# XMICRO-6502.net
KiCad netlist of a schematic drawn in EAGLE
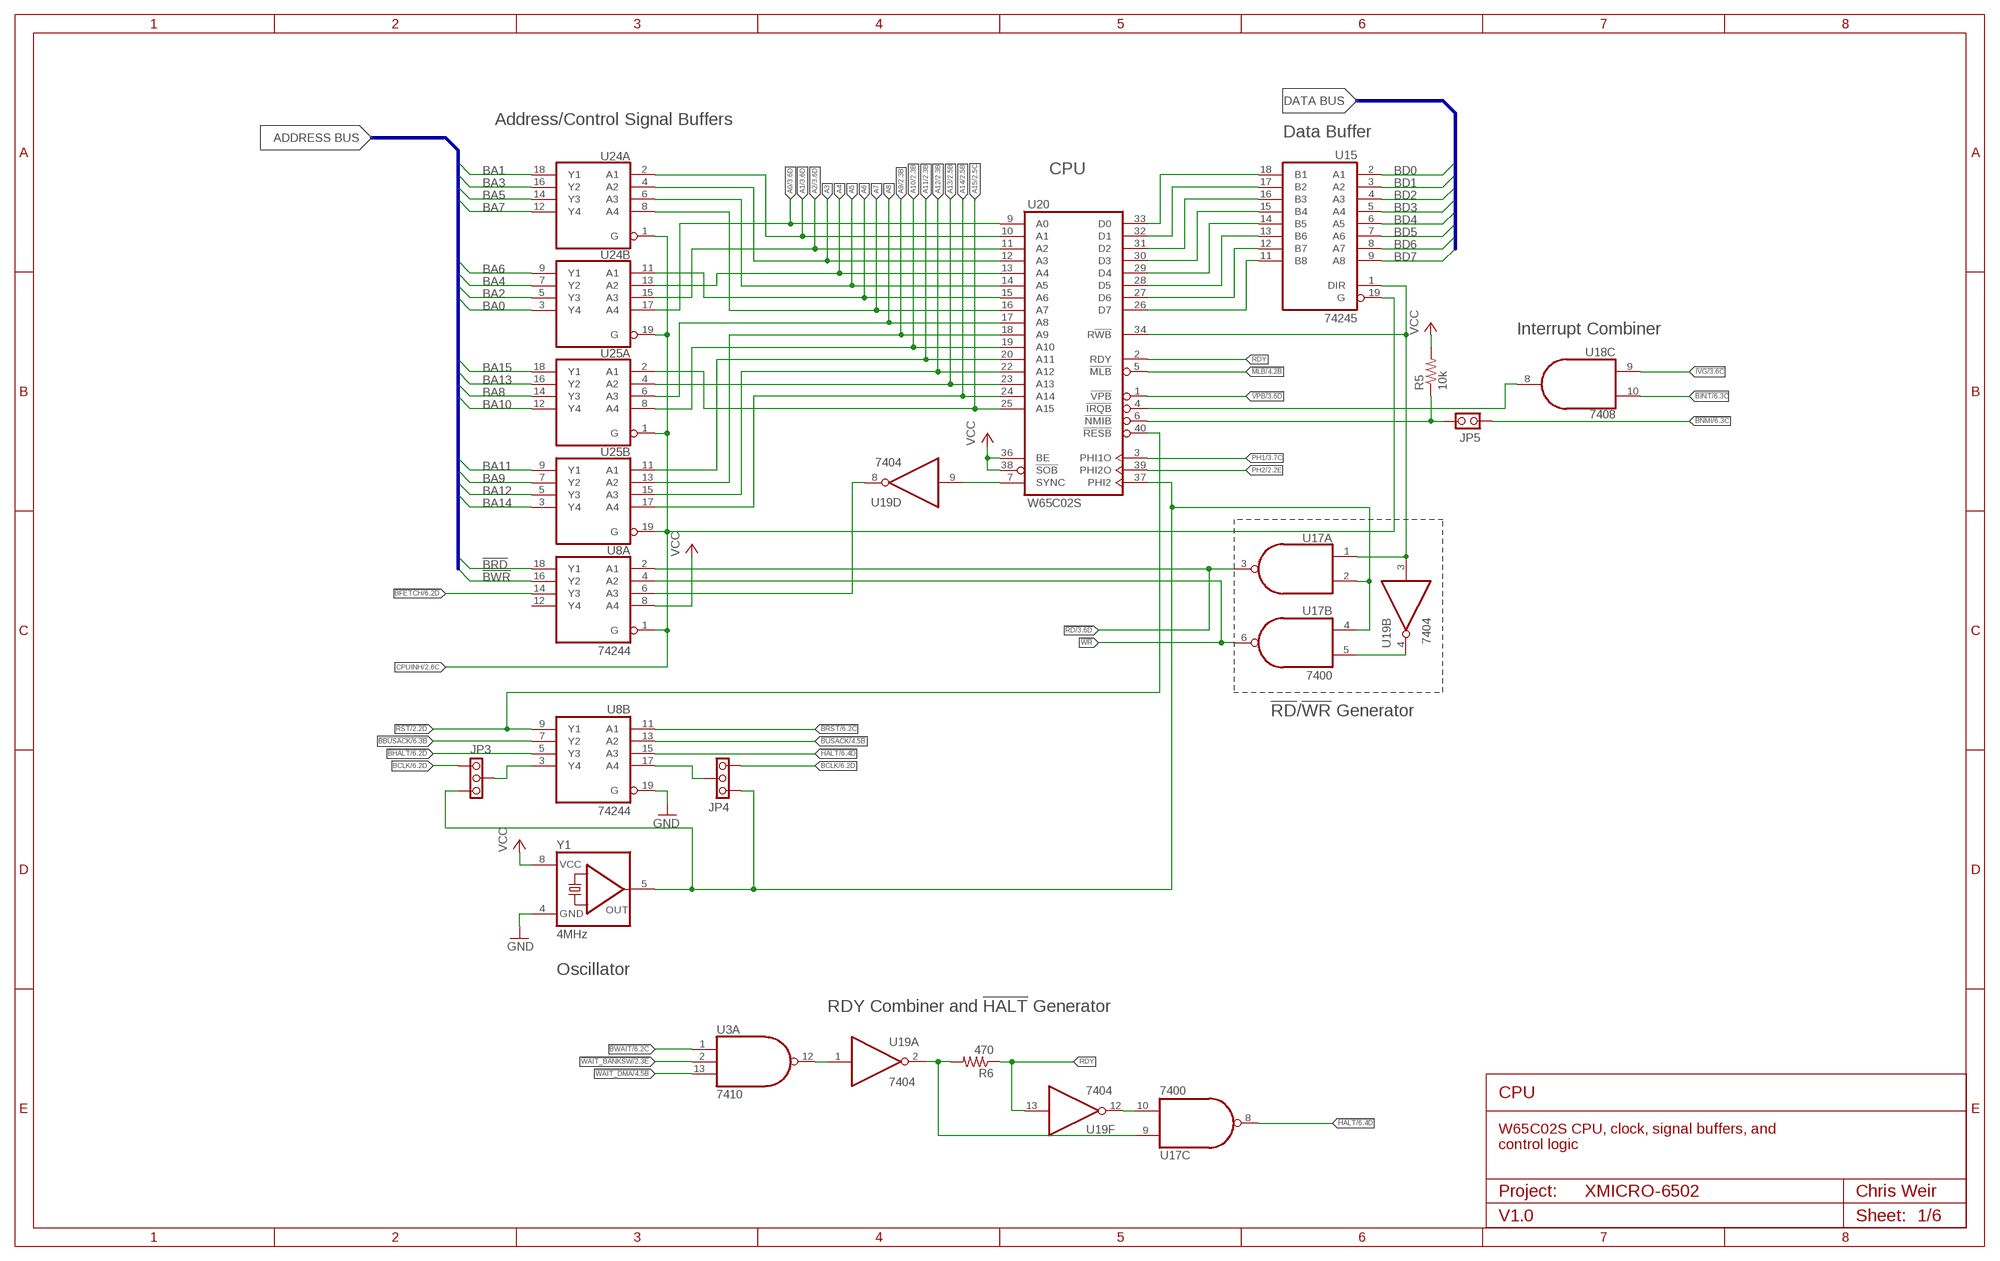
[diagram p0: schematic, sheet 1]
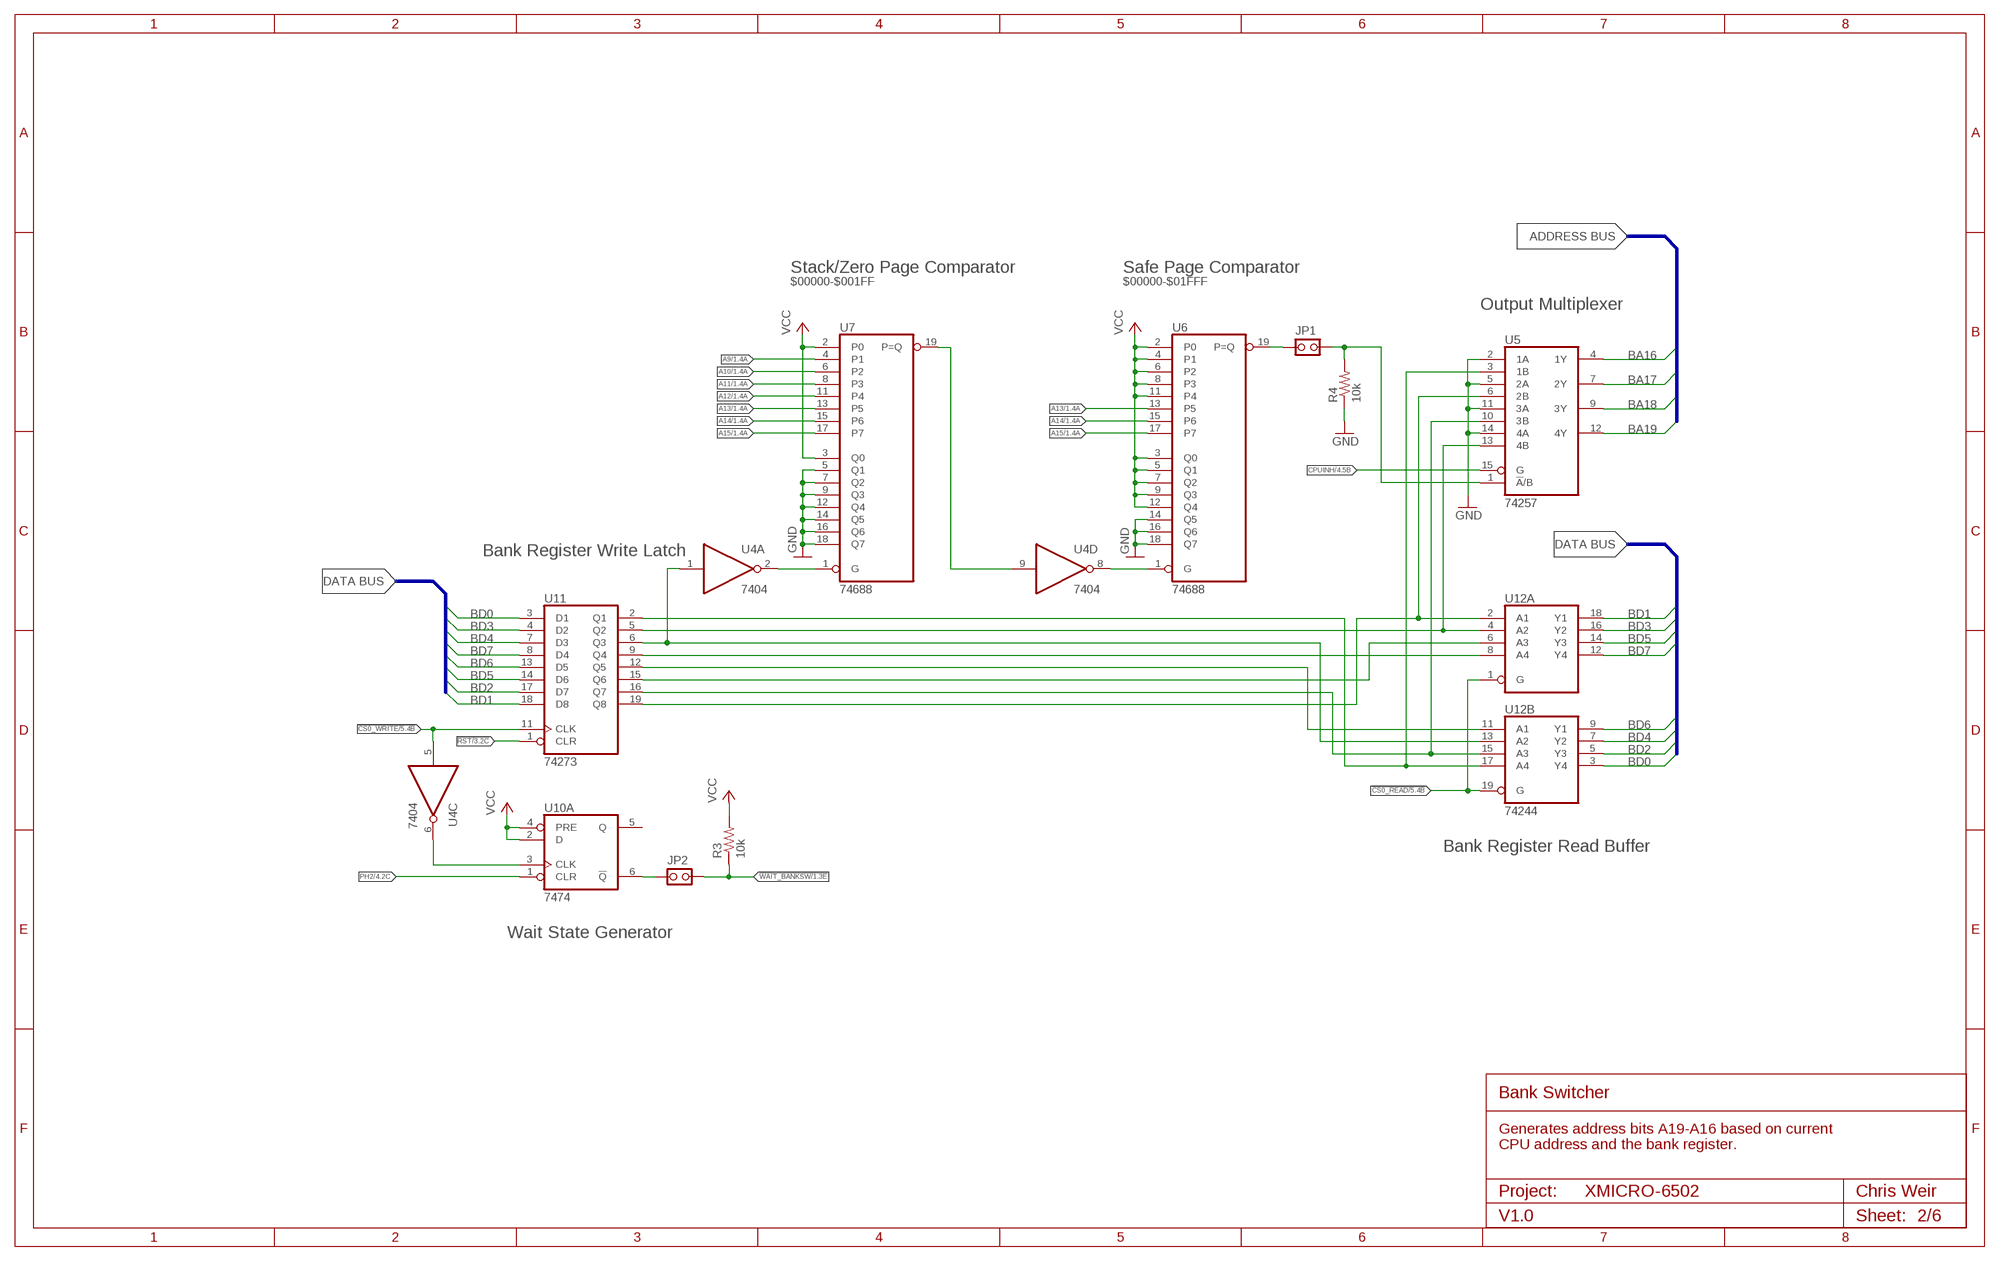
[diagram p1: schematic, sheet 2]
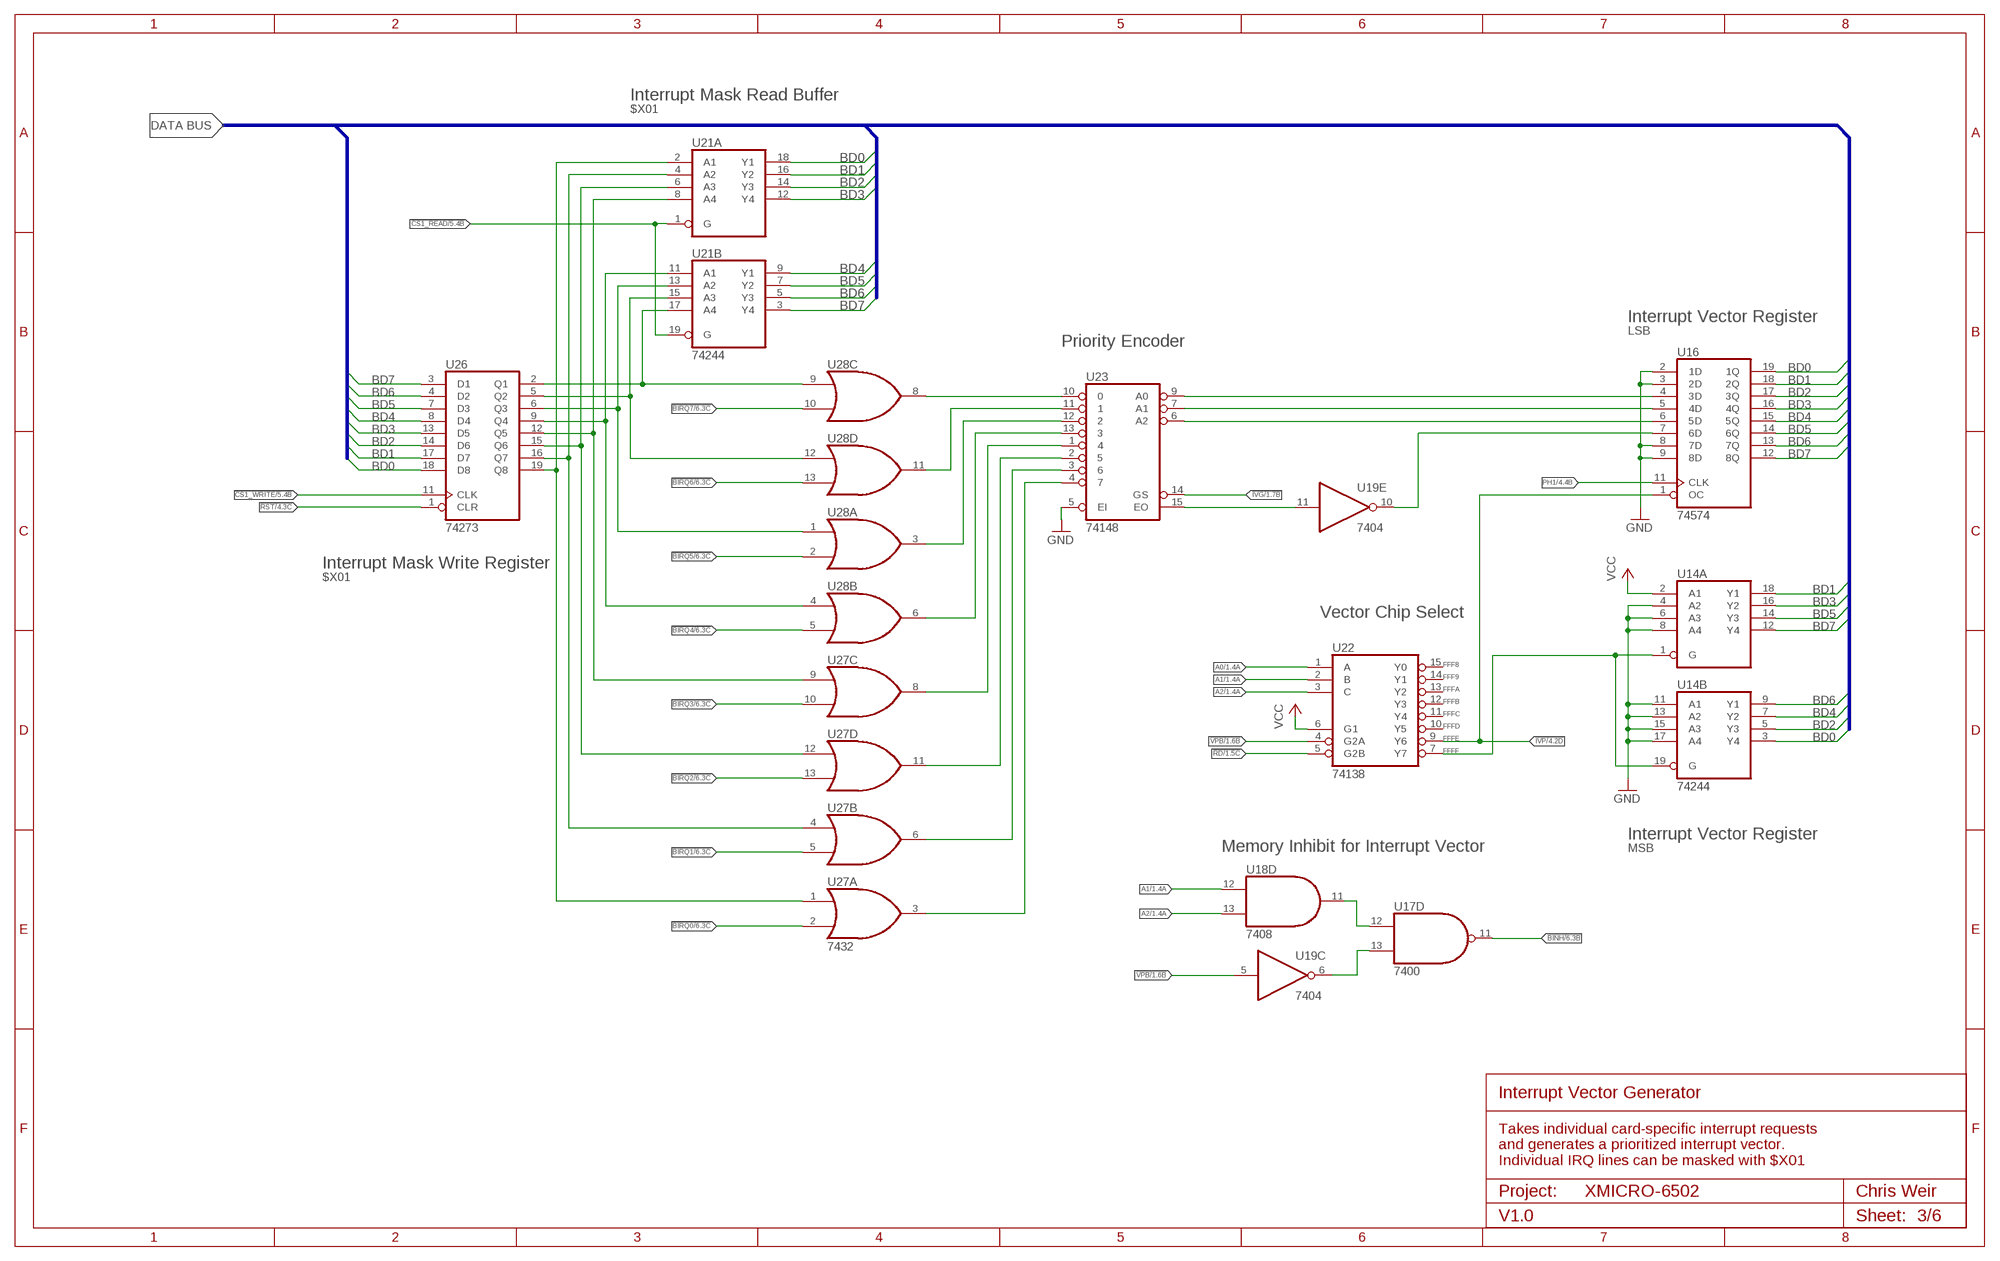
[diagram p2: schematic, sheet 3]
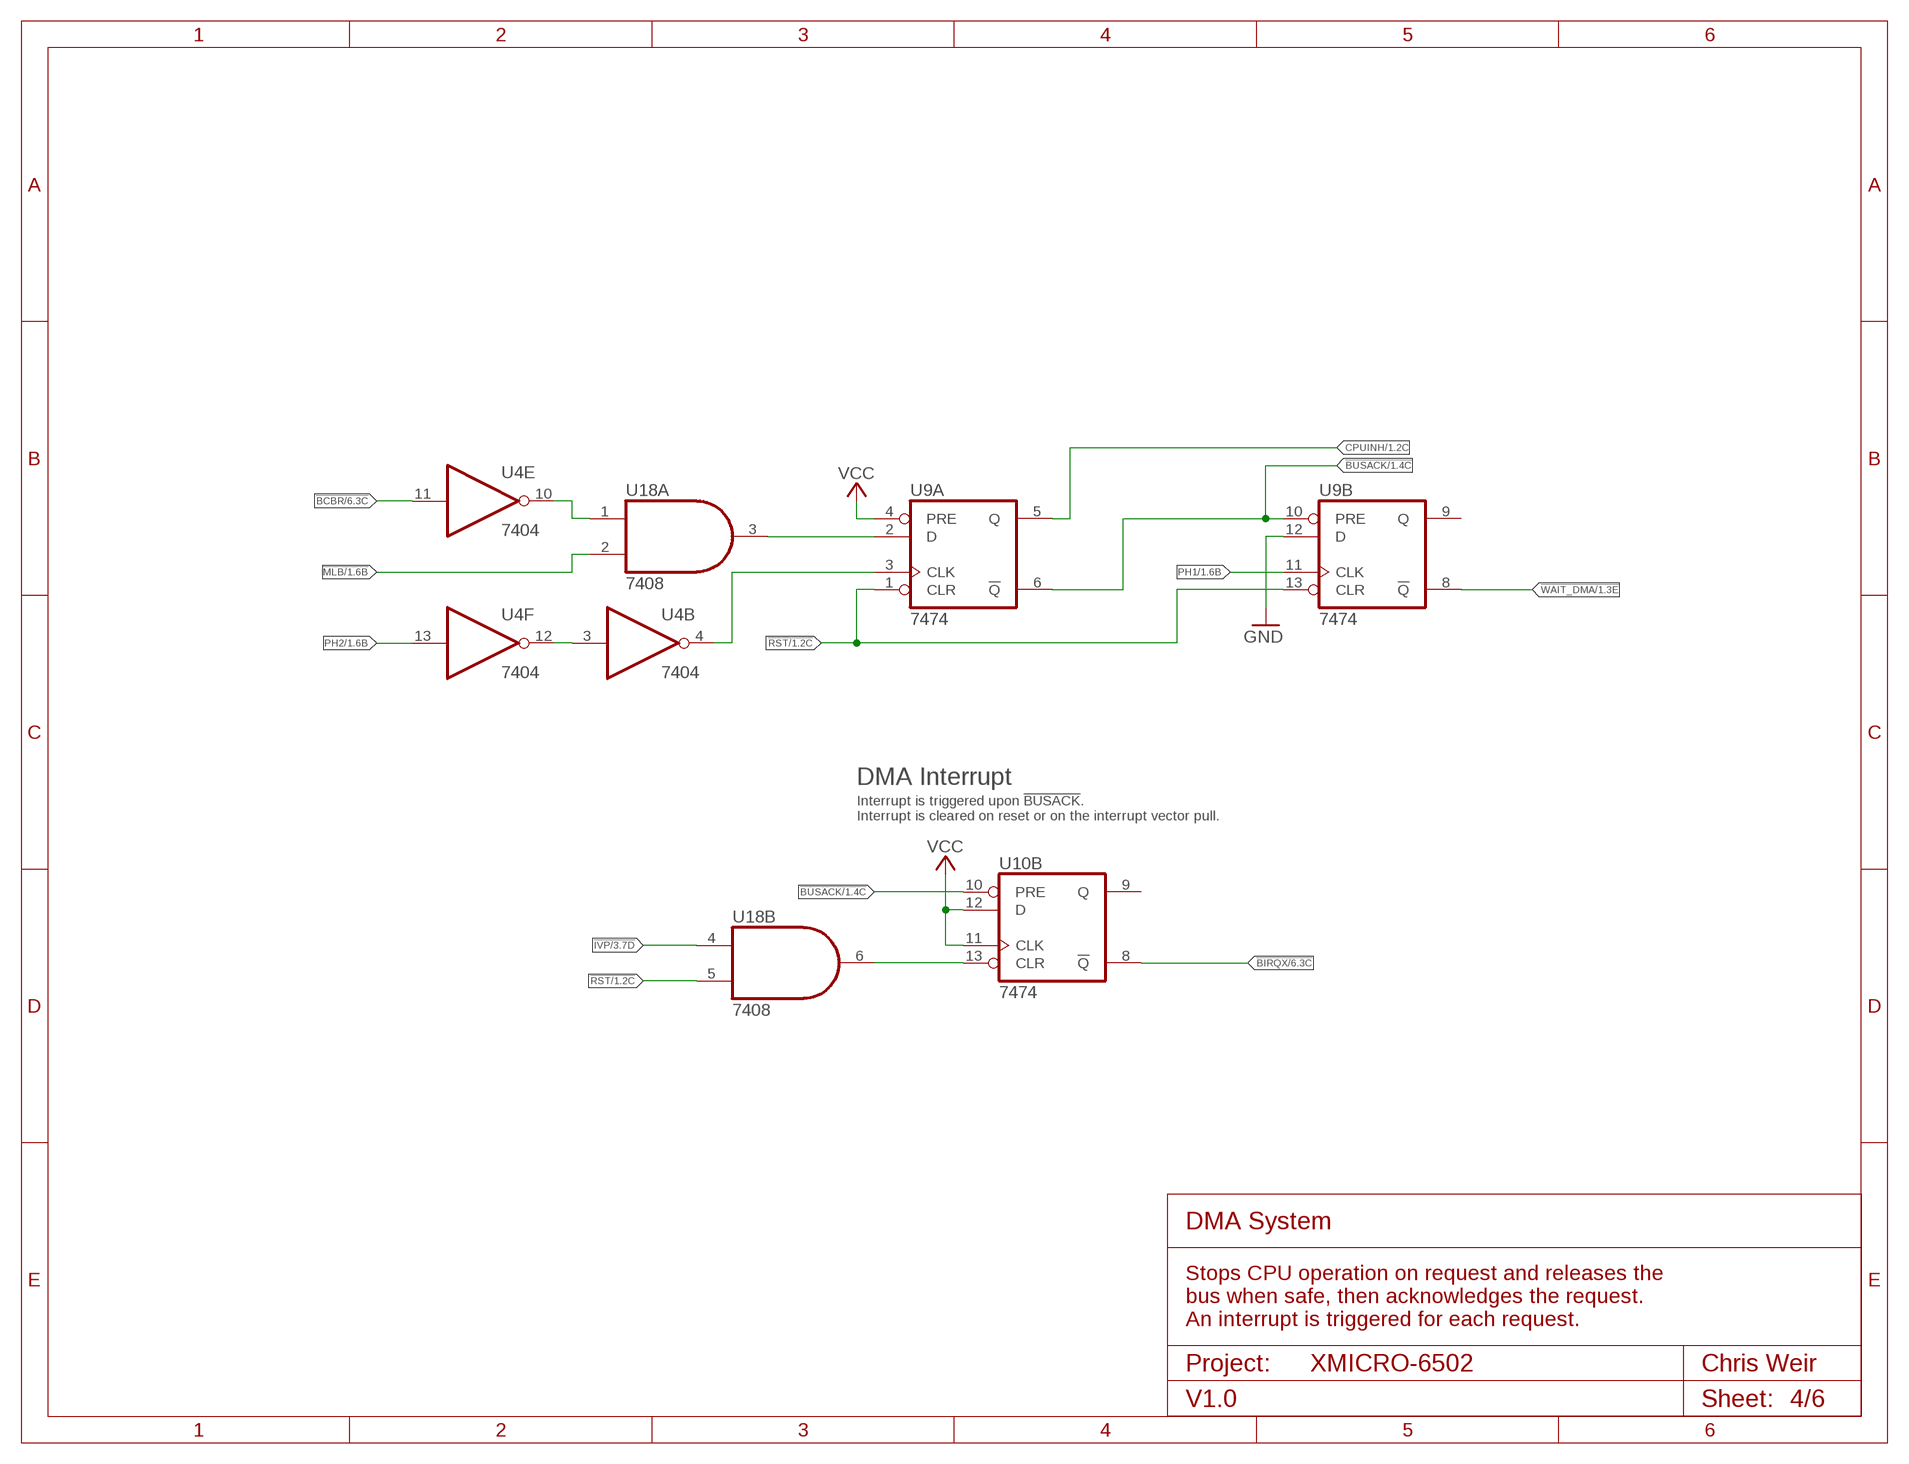
[diagram p3: schematic, sheet 4]
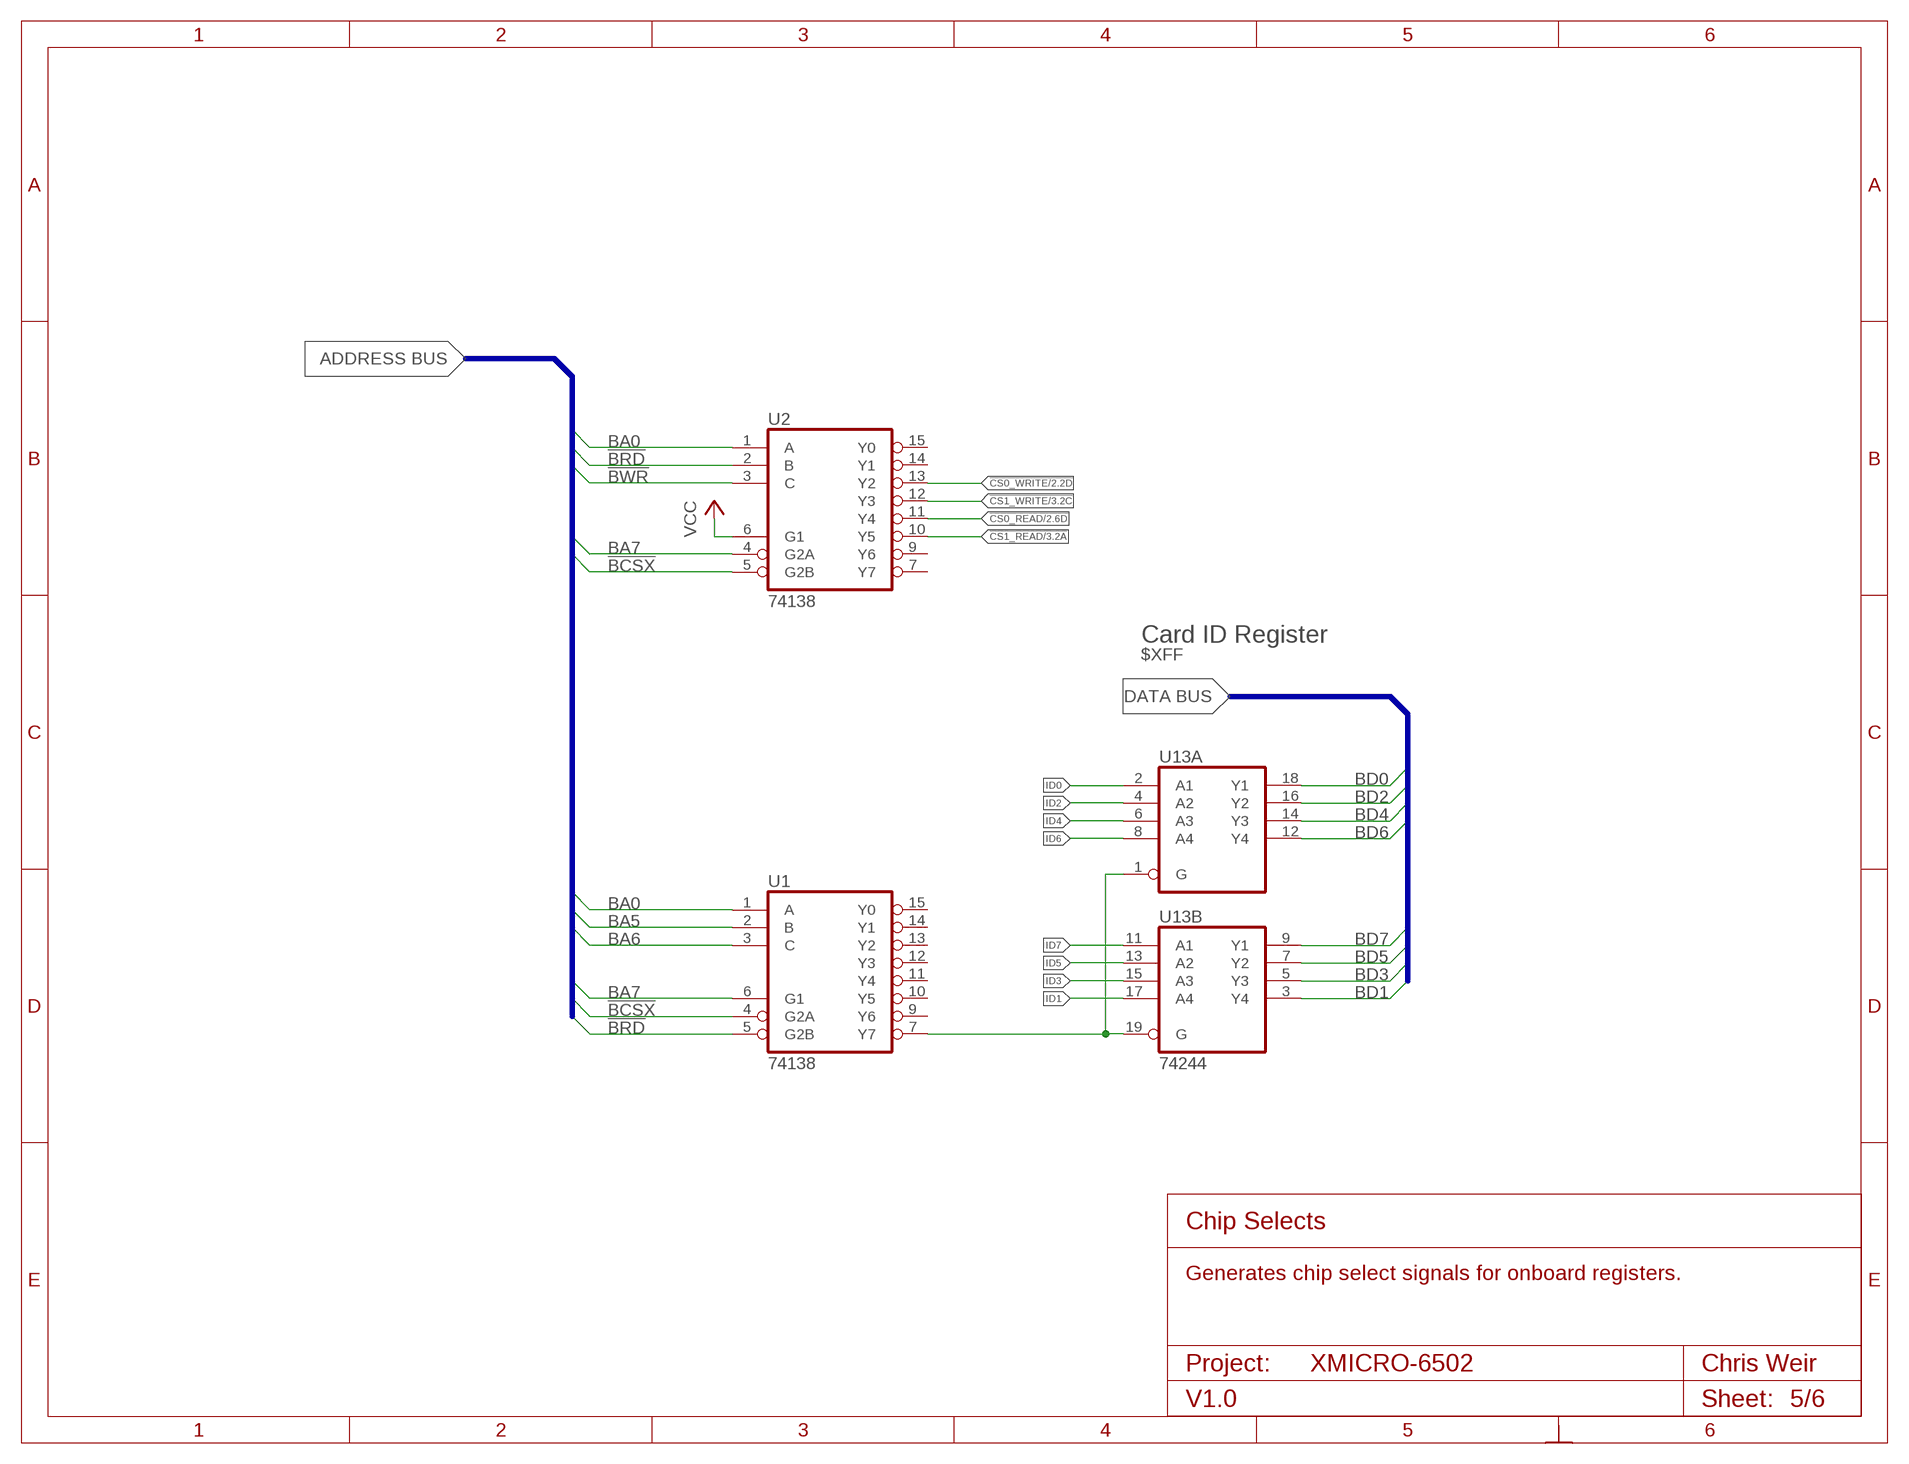
[diagram p4: schematic, sheet 5]
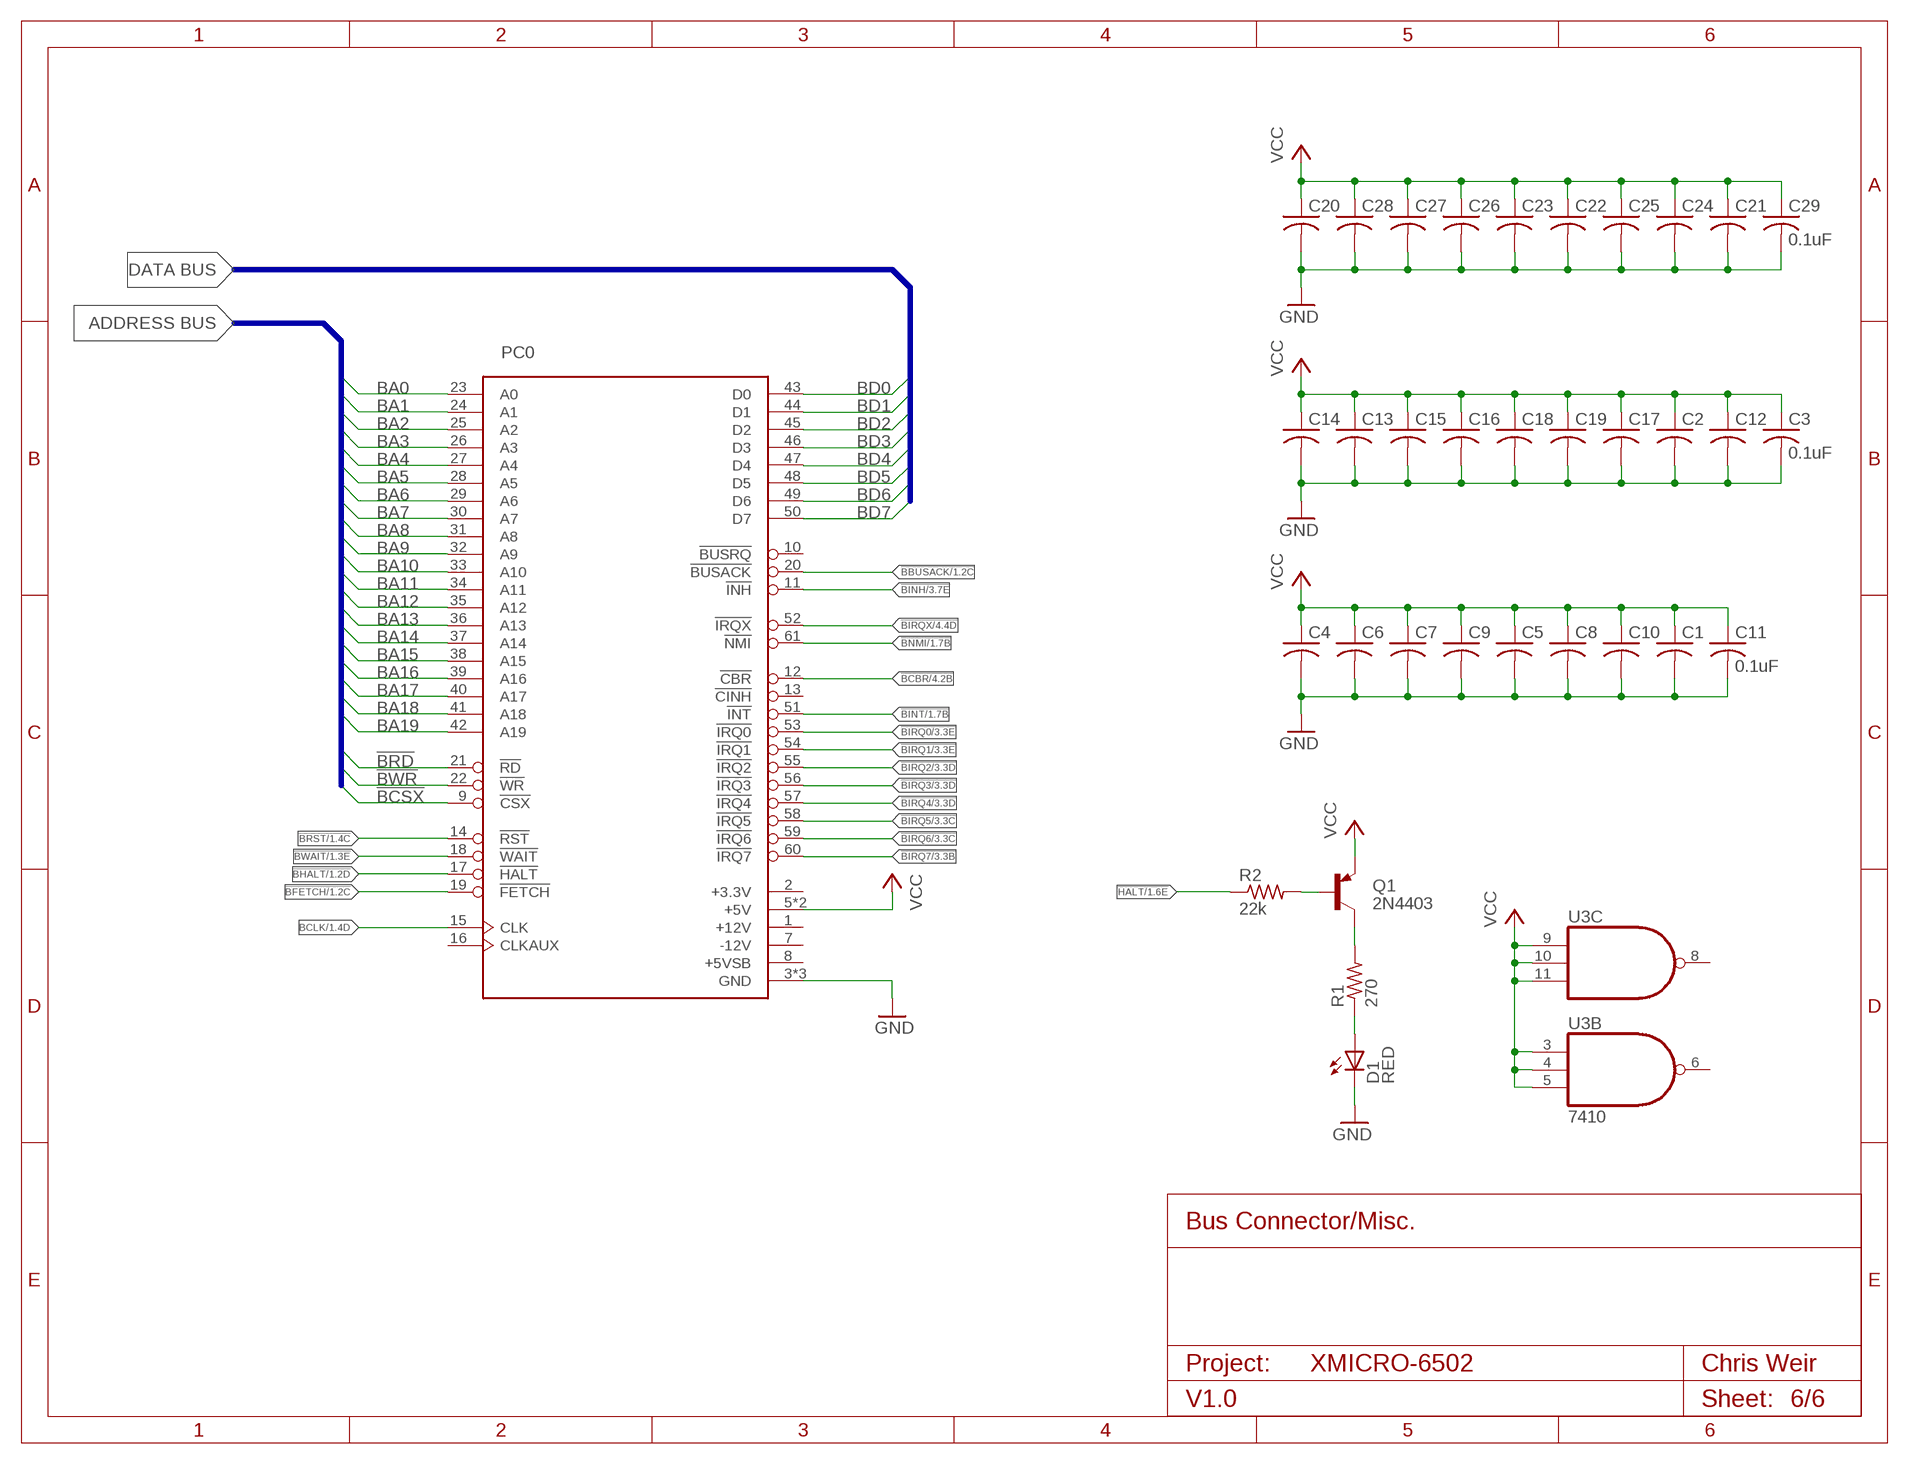
[diagram p5: schematic, sheet 6]

(export (version "E")
  (design (tool "Eeschema 10.0.6"))
  (components
    (comp (ref "JP1")
      (value "PINHD-1X2THRU")
      (footprint "eagle-import:1X02")
      (libsource (lib "eagle-import") (part "PINHD-1X2THRU"))
    )
    (comp (ref "JP2")
      (value "PINHD-1X2THRU")
      (footprint "eagle-import:1X02")
      (libsource (lib "eagle-import") (part "PINHD-1X2THRU"))
    )
    (comp (ref "R3")
      (value "10k")
      (footprint "eagle-import:0207_10")
      (libsource (lib "eagle-import") (part "R-US_0207/10"))
    )
    (comp (ref "R4")
      (value "10k")
      (footprint "eagle-import:0207_10")
      (libsource (lib "eagle-import") (part "R-US_0207/10"))
    )
    (comp (ref "U4")
      (value "7404")
      (footprint "eagle-import:DIL14")
      (libsource (lib "eagle-import") (part "7404NLS"))
    )
    (comp (ref "U5")
      (value "74257")
      (footprint "eagle-import:DIL16")
      (libsource (lib "eagle-import") (part "74257NLS"))
    )
    (comp (ref "U6")
      (value "74688")
      (footprint "eagle-import:DIL20")
      (libsource (lib "eagle-import") (part "74688NLS"))
    )
    (comp (ref "U7")
      (value "74688")
      (footprint "eagle-import:DIL20")
      (libsource (lib "eagle-import") (part "74688NLS"))
    )
    (comp (ref "U10")
      (value "7474")
      (footprint "eagle-import:DIL14")
      (libsource (lib "eagle-import") (part "7474NLS"))
    )
    (comp (ref "U11")
      (value "74273")
      (footprint "eagle-import:DIL20")
      (libsource (lib "eagle-import") (part "74273N"))
    )
    (comp (ref "U12")
      (value "74244")
      (footprint "eagle-import:DIL20")
      (libsource (lib "eagle-import") (part "74244NLS"))
    )
    (comp (ref "U14")
      (value "74244")
      (footprint "eagle-import:DIL20")
      (libsource (lib "eagle-import") (part "74244NLS"))
    )
    (comp (ref "U16")
      (value "74574")
      (footprint "eagle-import:DIL20")
      (libsource (lib "eagle-import") (part "74574NHC"))
    )
    (comp (ref "U17")
      (value "7400")
      (footprint "eagle-import:DIL14")
      (libsource (lib "eagle-import") (part "7400NLS"))
    )
    (comp (ref "U18")
      (value "7408")
      (footprint "eagle-import:DIL14")
      (libsource (lib "eagle-import") (part "7408NLS"))
    )
    (comp (ref "U19")
      (value "7404")
      (footprint "eagle-import:DIL14")
      (libsource (lib "eagle-import") (part "7404NLS"))
    )
    (comp (ref "U21")
      (value "74244")
      (footprint "eagle-import:DIL20")
      (libsource (lib "eagle-import") (part "74244NLS"))
    )
    (comp (ref "U22")
      (value "74138")
      (footprint "eagle-import:DIL16")
      (libsource (lib "eagle-import") (part "74138NLS"))
    )
    (comp (ref "U23")
      (value "74148")
      (footprint "eagle-import:DIL16")
      (libsource (lib "eagle-import") (part "74148NLS"))
    )
    (comp (ref "U26")
      (value "74273")
      (footprint "eagle-import:DIL20")
      (libsource (lib "eagle-import") (part "74273N"))
    )
    (comp (ref "U27")
      (value "7432")
      (footprint "eagle-import:DIL14")
      (libsource (lib "eagle-import") (part "7432NLS"))
    )
    (comp (ref "U28")
      (value "7432")
      (footprint "eagle-import:DIL14")
      (libsource (lib "eagle-import") (part "7432NLS"))
    )
    (comp (ref "U1")
      (value "74138")
      (footprint "eagle-import:DIL16")
      (libsource (lib "eagle-import") (part "74138NLS"))
    )
    (comp (ref "U2")
      (value "74138")
      (footprint "eagle-import:DIL16")
      (libsource (lib "eagle-import") (part "74138NLS"))
    )
    (comp (ref "U13")
      (value "74244")
      (footprint "eagle-import:DIL20")
      (libsource (lib "eagle-import") (part "74244NLS"))
    )
    (comp (ref "C1")
      (value "0.1uF")
      (footprint "eagle-import:C025-024X044")
      (libsource (lib "eagle-import") (part "C-US025-024X044"))
    )
    (comp (ref "C2")
      (value "0.1uF")
      (footprint "eagle-import:C025-024X044")
      (libsource (lib "eagle-import") (part "C-US025-024X044"))
    )
    (comp (ref "C3")
      (value "0.1uF")
      (footprint "eagle-import:C025-024X044")
      (libsource (lib "eagle-import") (part "C-US025-024X044"))
    )
    (comp (ref "C4")
      (value "0.1uF")
      (footprint "eagle-import:C025-024X044")
      (libsource (lib "eagle-import") (part "C-US025-024X044"))
    )
    (comp (ref "C5")
      (value "0.1uF")
      (footprint "eagle-import:C025-024X044")
      (libsource (lib "eagle-import") (part "C-US025-024X044"))
    )
    (comp (ref "C6")
      (value "0.1uF")
      (footprint "eagle-import:C025-024X044")
      (libsource (lib "eagle-import") (part "C-US025-024X044"))
    )
    (comp (ref "C7")
      (value "0.1uF")
      (footprint "eagle-import:C025-024X044")
      (libsource (lib "eagle-import") (part "C-US025-024X044"))
    )
    (comp (ref "C8")
      (value "0.1uF")
      (footprint "eagle-import:C025-024X044")
      (libsource (lib "eagle-import") (part "C-US025-024X044"))
    )
    (comp (ref "C9")
      (value "0.1uF")
      (footprint "eagle-import:C025-024X044")
      (libsource (lib "eagle-import") (part "C-US025-024X044"))
    )
    (comp (ref "C10")
      (value "0.1uF")
      (footprint "eagle-import:C025-024X044")
      (libsource (lib "eagle-import") (part "C-US025-024X044"))
    )
    (comp (ref "C11")
      (value "0.1uF")
      (footprint "eagle-import:C025-024X044")
      (libsource (lib "eagle-import") (part "C-US025-024X044"))
    )
    (comp (ref "C12")
      (value "0.1uF")
      (footprint "eagle-import:C025-024X044")
      (libsource (lib "eagle-import") (part "C-US025-024X044"))
    )
    (comp (ref "C13")
      (value "0.1uF")
      (footprint "eagle-import:C025-024X044")
      (libsource (lib "eagle-import") (part "C-US025-024X044"))
    )
    (comp (ref "C14")
      (value "0.1uF")
      (footprint "eagle-import:C025-024X044")
      (libsource (lib "eagle-import") (part "C-US025-024X044"))
    )
    (comp (ref "C15")
      (value "0.1uF")
      (footprint "eagle-import:C025-024X044")
      (libsource (lib "eagle-import") (part "C-US025-024X044"))
    )
    (comp (ref "C16")
      (value "0.1uF")
      (footprint "eagle-import:C025-024X044")
      (libsource (lib "eagle-import") (part "C-US025-024X044"))
    )
    (comp (ref "C17")
      (value "0.1uF")
      (footprint "eagle-import:C025-024X044")
      (libsource (lib "eagle-import") (part "C-US025-024X044"))
    )
    (comp (ref "C18")
      (value "0.1uF")
      (footprint "eagle-import:C025-024X044")
      (libsource (lib "eagle-import") (part "C-US025-024X044"))
    )
    (comp (ref "C19")
      (value "0.1uF")
      (footprint "eagle-import:C025-024X044")
      (libsource (lib "eagle-import") (part "C-US025-024X044"))
    )
    (comp (ref "C20")
      (value "0.1uF")
      (footprint "eagle-import:C025-024X044")
      (libsource (lib "eagle-import") (part "C-US025-024X044"))
    )
    (comp (ref "C21")
      (value "0.1uF")
      (footprint "eagle-import:C025-024X044")
      (libsource (lib "eagle-import") (part "C-US025-024X044"))
    )
    (comp (ref "C22")
      (value "0.1uF")
      (footprint "eagle-import:C025-024X044")
      (libsource (lib "eagle-import") (part "C-US025-024X044"))
    )
    (comp (ref "C23")
      (value "0.1uF")
      (footprint "eagle-import:C025-024X044")
      (libsource (lib "eagle-import") (part "C-US025-024X044"))
    )
    (comp (ref "C24")
      (value "0.1uF")
      (footprint "eagle-import:C025-024X044")
      (libsource (lib "eagle-import") (part "C-US025-024X044"))
    )
    (comp (ref "C25")
      (value "0.1uF")
      (footprint "eagle-import:C025-024X044")
      (libsource (lib "eagle-import") (part "C-US025-024X044"))
    )
    (comp (ref "C26")
      (value "0.1uF")
      (footprint "eagle-import:C025-024X044")
      (libsource (lib "eagle-import") (part "C-US025-024X044"))
    )
    (comp (ref "C27")
      (value "0.1uF")
      (footprint "eagle-import:C025-024X044")
      (libsource (lib "eagle-import") (part "C-US025-024X044"))
    )
    (comp (ref "C28")
      (value "0.1uF")
      (footprint "eagle-import:C025-024X044")
      (libsource (lib "eagle-import") (part "C-US025-024X044"))
    )
    (comp (ref "C29")
      (value "0.1uF")
      (footprint "eagle-import:C025-024X044")
      (libsource (lib "eagle-import") (part "C-US025-024X044"))
    )
    (comp (ref "D1")
      (value "RED")
      (footprint "eagle-import:LED5MM")
      (libsource (lib "eagle-import") (part "LED5MM"))
    )
    (comp (ref "PC0")
      (value "XMICRO-BUS-EDGE62M")
      (footprint "eagle-import:EDGE62M")
      (libsource (lib "eagle-import") (part "XMICRO-BUS-EDGE62M"))
    )
    (comp (ref "Q1")
      (value "2N4403")
      (footprint "eagle-import:TO92")
      (libsource (lib "eagle-import") (part "TRANSISTOR-PNP-2N4403"))
    )
    (comp (ref "R1")
      (value "270")
      (footprint "eagle-import:0207_10")
      (libsource (lib "eagle-import") (part "R-US_0207/10"))
    )
    (comp (ref "R2")
      (value "22k")
      (footprint "eagle-import:0207_10")
      (libsource (lib "eagle-import") (part "R-US_0207/10"))
    )
    (comp (ref "U3")
      (value "7410")
      (footprint "eagle-import:DIL14")
      (libsource (lib "eagle-import") (part "7410NLS"))
    )
    (comp (ref "U9")
      (value "7474")
      (footprint "eagle-import:DIL14")
      (libsource (lib "eagle-import") (part "7474NLS"))
    )
    (comp (ref "JP3")
      (value "PINHD1X3THRU")
      (footprint "eagle-import:1X03")
      (libsource (lib "eagle-import") (part "PINHD1X3THRU"))
    )
    (comp (ref "JP4")
      (value "PINHD1X3THRU")
      (footprint "eagle-import:1X03")
      (libsource (lib "eagle-import") (part "PINHD1X3THRU"))
    )
    (comp (ref "JP5")
      (value "PINHD-1X2THRU")
      (footprint "eagle-import:1X02")
      (libsource (lib "eagle-import") (part "PINHD-1X2THRU"))
    )
    (comp (ref "R5")
      (value "10k")
      (footprint "eagle-import:0207_10")
      (libsource (lib "eagle-import") (part "R-US_0207/10"))
    )
    (comp (ref "R6")
      (value "470")
      (footprint "eagle-import:0207_10")
      (libsource (lib "eagle-import") (part "R-US_0207/10"))
    )
    (comp (ref "U8")
      (value "74244")
      (footprint "eagle-import:DIL20")
      (libsource (lib "eagle-import") (part "74244NLS"))
    )
    (comp (ref "U15")
      (value "74245")
      (footprint "eagle-import:DIL20")
      (libsource (lib "eagle-import") (part "74245NLS"))
    )
    (comp (ref "U20")
      (value "W65C02S")
      (footprint "eagle-import:DIL40")
      (libsource (lib "eagle-import") (part "W65C02P"))
    )
    (comp (ref "U24")
      (value "74244")
      (footprint "eagle-import:DIL20")
      (libsource (lib "eagle-import") (part "74244NLS"))
    )
    (comp (ref "U25")
      (value "74244")
      (footprint "eagle-import:DIL20")
      (libsource (lib "eagle-import") (part "74244NLS"))
    )
    (comp (ref "Y1")
      (value "4MHz")
      (footprint "eagle-import:DIL08S")
      (libsource (lib "eagle-import") (part "QG5460"))
    )
  )
  (nets
    (net (code "2") (name "A0") (class "Default")
      (node (ref "U20") (pin "9") (pinfunction "A0_9") (pintype "output"))
      (node (ref "U22") (pin "1") (pinfunction "A_1") (pintype "input"))
      (node (ref "U24") (pin "17") (pinfunction "A4_17") (pintype "input"))
    )
    (net (code "3") (name "A1") (class "Default")
      (node (ref "U18") (pin "12") (pinfunction "I0_12") (pintype "input"))
      (node (ref "U20") (pin "10") (pinfunction "A1_10") (pintype "output"))
      (node (ref "U22") (pin "2") (pinfunction "B_2") (pintype "input"))
      (node (ref "U24") (pin "2") (pinfunction "A1_2") (pintype "input"))
    )
    (net (code "4") (name "A2") (class "Default")
      (node (ref "U18") (pin "13") (pinfunction "I1_13") (pintype "input"))
      (node (ref "U20") (pin "11") (pinfunction "A2_11") (pintype "output"))
      (node (ref "U22") (pin "3") (pinfunction "C_3") (pintype "input"))
      (node (ref "U24") (pin "15") (pinfunction "A3_15") (pintype "input"))
    )
    (net (code "5") (name "A3") (class "Default")
      (node (ref "U20") (pin "12") (pinfunction "A3_12") (pintype "output"))
      (node (ref "U24") (pin "4") (pinfunction "A2_4") (pintype "input"))
    )
    (net (code "6") (name "A4") (class "Default")
      (node (ref "U20") (pin "13") (pinfunction "A4_13") (pintype "output"))
      (node (ref "U24") (pin "13") (pinfunction "A2_13") (pintype "input"))
    )
    (net (code "7") (name "A5") (class "Default")
      (node (ref "U20") (pin "14") (pinfunction "A5_14") (pintype "output"))
      (node (ref "U24") (pin "6") (pinfunction "A3_6") (pintype "input"))
    )
    (net (code "8") (name "A6") (class "Default")
      (node (ref "U20") (pin "15") (pinfunction "A6_15") (pintype "output"))
      (node (ref "U24") (pin "11") (pinfunction "A1_11") (pintype "input"))
    )
    (net (code "9") (name "A7") (class "Default")
      (node (ref "U20") (pin "16") (pinfunction "A7_16") (pintype "output"))
      (node (ref "U24") (pin "8") (pinfunction "A4_8") (pintype "input"))
    )
    (net (code "10") (name "A8") (class "Default")
      (node (ref "U20") (pin "17") (pinfunction "A8_17") (pintype "output"))
      (node (ref "U25") (pin "6") (pinfunction "A3_6") (pintype "input"))
    )
    (net (code "11") (name "A9") (class "Default")
      (node (ref "U20") (pin "18") (pinfunction "A9_18") (pintype "output"))
      (node (ref "U25") (pin "13") (pinfunction "A2_13") (pintype "input"))
      (node (ref "U7") (pin "4") (pinfunction "P1_4") (pintype "input"))
    )
    (net (code "12") (name "A10") (class "Default")
      (node (ref "U20") (pin "19") (pinfunction "A10_19") (pintype "output"))
      (node (ref "U25") (pin "8") (pinfunction "A4_8") (pintype "input"))
      (node (ref "U7") (pin "6") (pinfunction "P2_6") (pintype "input"))
    )
    (net (code "13") (name "A11") (class "Default")
      (node (ref "U20") (pin "20") (pinfunction "A11_20") (pintype "output"))
      (node (ref "U25") (pin "11") (pinfunction "A1_11") (pintype "input"))
      (node (ref "U7") (pin "8") (pinfunction "P3_8") (pintype "input"))
    )
    (net (code "14") (name "A12") (class "Default")
      (node (ref "U20") (pin "22") (pinfunction "A12_22") (pintype "output"))
      (node (ref "U25") (pin "15") (pinfunction "A3_15") (pintype "input"))
      (node (ref "U7") (pin "11") (pinfunction "P4_11") (pintype "input"))
    )
    (net (code "15") (name "A13") (class "Default")
      (node (ref "U20") (pin "23") (pinfunction "A13_23") (pintype "output"))
      (node (ref "U25") (pin "4") (pinfunction "A2_4") (pintype "input"))
      (node (ref "U6") (pin "13") (pinfunction "P5_13") (pintype "input"))
      (node (ref "U7") (pin "13") (pinfunction "P5_13") (pintype "input"))
    )
    (net (code "16") (name "A14") (class "Default")
      (node (ref "U20") (pin "24") (pinfunction "A14_24") (pintype "output"))
      (node (ref "U25") (pin "17") (pinfunction "A4_17") (pintype "input"))
      (node (ref "U6") (pin "15") (pinfunction "P6_15") (pintype "input"))
      (node (ref "U7") (pin "15") (pinfunction "P6_15") (pintype "input"))
    )
    (net (code "17") (name "A15") (class "Default")
      (node (ref "U20") (pin "25") (pinfunction "A15_25") (pintype "output"))
      (node (ref "U25") (pin "2") (pinfunction "A1_2") (pintype "input"))
      (node (ref "U6") (pin "17") (pinfunction "P7_17") (pintype "input"))
      (node (ref "U7") (pin "17") (pinfunction "P7_17") (pintype "input"))
    )
    (net (code "18") (name "BA0") (class "Default")
      (node (ref "PC0") (pin "23") (pinfunction "A0_23") (pintype "bidirectional"))
      (node (ref "U1") (pin "1") (pinfunction "A_1") (pintype "input"))
      (node (ref "U2") (pin "1") (pinfunction "A_1") (pintype "input"))
      (node (ref "U24") (pin "3") (pinfunction "Y4_3") (pintype "tri_state"))
    )
    (net (code "19") (name "BA1") (class "Default")
      (node (ref "PC0") (pin "24") (pinfunction "A1_24") (pintype "bidirectional"))
      (node (ref "U24") (pin "18") (pinfunction "Y1_18") (pintype "tri_state"))
    )
    (net (code "20") (name "BA2") (class "Default")
      (node (ref "PC0") (pin "25") (pinfunction "A2_25") (pintype "bidirectional"))
      (node (ref "U24") (pin "5") (pinfunction "Y3_5") (pintype "tri_state"))
    )
    (net (code "21") (name "BA3") (class "Default")
      (node (ref "PC0") (pin "26") (pinfunction "A3_26") (pintype "bidirectional"))
      (node (ref "U24") (pin "16") (pinfunction "Y2_16") (pintype "tri_state"))
    )
    (net (code "22") (name "BA4") (class "Default")
      (node (ref "PC0") (pin "27") (pinfunction "A4_27") (pintype "bidirectional"))
      (node (ref "U24") (pin "7") (pinfunction "Y2_7") (pintype "tri_state"))
    )
    (net (code "23") (name "BA5") (class "Default")
      (node (ref "PC0") (pin "28") (pinfunction "A5_28") (pintype "bidirectional"))
      (node (ref "U1") (pin "2") (pinfunction "B_2") (pintype "input"))
      (node (ref "U24") (pin "14") (pinfunction "Y3_14") (pintype "tri_state"))
    )
    (net (code "24") (name "BA6") (class "Default")
      (node (ref "PC0") (pin "29") (pinfunction "A6_29") (pintype "bidirectional"))
      (node (ref "U1") (pin "3") (pinfunction "C_3") (pintype "input"))
      (node (ref "U24") (pin "9") (pinfunction "Y1_9") (pintype "tri_state"))
    )
    (net (code "25") (name "BA7") (class "Default")
      (node (ref "PC0") (pin "30") (pinfunction "A7_30") (pintype "bidirectional"))
      (node (ref "U1") (pin "6") (pinfunction "G1_6") (pintype "input"))
      (node (ref "U2") (pin "4") (pinfunction "G2A_4") (pintype "input"))
      (node (ref "U24") (pin "12") (pinfunction "Y4_12") (pintype "tri_state"))
    )
    (net (code "26") (name "BA8") (class "Default")
      (node (ref "PC0") (pin "31") (pinfunction "A8_31") (pintype "bidirectional"))
      (node (ref "U25") (pin "14") (pinfunction "Y3_14") (pintype "tri_state"))
    )
    (net (code "27") (name "BA9") (class "Default")
      (node (ref "PC0") (pin "32") (pinfunction "A9_32") (pintype "bidirectional"))
      (node (ref "U25") (pin "7") (pinfunction "Y2_7") (pintype "tri_state"))
    )
    (net (code "28") (name "BA10") (class "Default")
      (node (ref "PC0") (pin "33") (pinfunction "A10_33") (pintype "bidirectional"))
      (node (ref "U25") (pin "12") (pinfunction "Y4_12") (pintype "tri_state"))
    )
    (net (code "29") (name "BA11") (class "Default")
      (node (ref "PC0") (pin "34") (pinfunction "A11_34") (pintype "bidirectional"))
      (node (ref "U25") (pin "9") (pinfunction "Y1_9") (pintype "tri_state"))
    )
    (net (code "30") (name "BA12") (class "Default")
      (node (ref "PC0") (pin "35") (pinfunction "A12_35") (pintype "bidirectional"))
      (node (ref "U25") (pin "5") (pinfunction "Y3_5") (pintype "tri_state"))
    )
    (net (code "31") (name "BA13") (class "Default")
      (node (ref "PC0") (pin "36") (pinfunction "A13_36") (pintype "bidirectional"))
      (node (ref "U25") (pin "16") (pinfunction "Y2_16") (pintype "tri_state"))
    )
    (net (code "32") (name "BA14") (class "Default")
      (node (ref "PC0") (pin "37") (pinfunction "A14_37") (pintype "bidirectional"))
      (node (ref "U25") (pin "3") (pinfunction "Y4_3") (pintype "tri_state"))
    )
    (net (code "33") (name "BA15") (class "Default")
      (node (ref "PC0") (pin "38") (pinfunction "A15_38") (pintype "bidirectional"))
      (node (ref "U25") (pin "18") (pinfunction "Y1_18") (pintype "tri_state"))
    )
    (net (code "34") (name "BA16") (class "Default")
      (node (ref "PC0") (pin "39") (pinfunction "A16_39") (pintype "bidirectional"))
      (node (ref "U5") (pin "4") (pinfunction "1Y_4") (pintype "tri_state"))
    )
    (net (code "35") (name "BA17") (class "Default")
      (node (ref "PC0") (pin "40") (pinfunction "A17_40") (pintype "bidirectional"))
      (node (ref "U5") (pin "7") (pinfunction "2Y_7") (pintype "tri_state"))
    )
    (net (code "36") (name "BA18") (class "Default")
      (node (ref "PC0") (pin "41") (pinfunction "A18_41") (pintype "bidirectional"))
      (node (ref "U5") (pin "9") (pinfunction "3Y_9") (pintype "tri_state"))
    )
    (net (code "37") (name "BA19") (class "Default")
      (node (ref "PC0") (pin "42") (pinfunction "A19_42") (pintype "bidirectional"))
      (node (ref "U5") (pin "12") (pinfunction "4Y_12") (pintype "tri_state"))
    )
    (net (code "38") (name "BCLK") (class "Default")
      (node (ref "JP3") (pin "1") (pinfunction "1_1") (pintype "passive"))
      (node (ref "JP4") (pin "3") (pinfunction "3_3") (pintype "passive"))
      (node (ref "PC0") (pin "15") (pinfunction "CLK_15") (pintype "bidirectional"))
    )
    (net (code "39") (name "BD0") (class "Default")
      (node (ref "PC0") (pin "43") (pinfunction "D0_43") (pintype "bidirectional"))
      (node (ref "U11") (pin "3") (pinfunction "D1_3") (pintype "input"))
      (node (ref "U12") (pin "3") (pinfunction "Y4_3") (pintype "tri_state"))
      (node (ref "U13") (pin "18") (pinfunction "Y1_18") (pintype "tri_state"))
      (node (ref "U14") (pin "3") (pinfunction "Y4_3") (pintype "tri_state"))
      (node (ref "U15") (pin "2") (pinfunction "A1_2") (pintype "bidirectional"))
      (node (ref "U16") (pin "19") (pinfunction "1Q_19") (pintype "tri_state"))
      (node (ref "U21") (pin "18") (pinfunction "Y1_18") (pintype "tri_state"))
      (node (ref "U26") (pin "18") (pinfunction "D8_18") (pintype "input"))
    )
    (net (code "40") (name "BD1") (class "Default")
      (node (ref "PC0") (pin "44") (pinfunction "D1_44") (pintype "bidirectional"))
      (node (ref "U11") (pin "18") (pinfunction "D8_18") (pintype "input"))
      (node (ref "U12") (pin "18") (pinfunction "Y1_18") (pintype "tri_state"))
      (node (ref "U13") (pin "3") (pinfunction "Y4_3") (pintype "tri_state"))
      (node (ref "U14") (pin "18") (pinfunction "Y1_18") (pintype "tri_state"))
      (node (ref "U15") (pin "3") (pinfunction "A2_3") (pintype "bidirectional"))
      (node (ref "U16") (pin "18") (pinfunction "2Q_18") (pintype "tri_state"))
      (node (ref "U21") (pin "16") (pinfunction "Y2_16") (pintype "tri_state"))
      (node (ref "U26") (pin "17") (pinfunction "D7_17") (pintype "input"))
    )
    (net (code "41") (name "BD2") (class "Default")
      (node (ref "PC0") (pin "45") (pinfunction "D2_45") (pintype "bidirectional"))
      (node (ref "U11") (pin "17") (pinfunction "D7_17") (pintype "input"))
      (node (ref "U12") (pin "5") (pinfunction "Y3_5") (pintype "tri_state"))
      (node (ref "U13") (pin "16") (pinfunction "Y2_16") (pintype "tri_state"))
      (node (ref "U14") (pin "5") (pinfunction "Y3_5") (pintype "tri_state"))
      (node (ref "U15") (pin "4") (pinfunction "A3_4") (pintype "bidirectional"))
      (node (ref "U16") (pin "17") (pinfunction "3Q_17") (pintype "tri_state"))
      (node (ref "U21") (pin "14") (pinfunction "Y3_14") (pintype "tri_state"))
      (node (ref "U26") (pin "14") (pinfunction "D6_14") (pintype "input"))
    )
    (net (code "42") (name "BD3") (class "Default")
      (node (ref "PC0") (pin "46") (pinfunction "D3_46") (pintype "bidirectional"))
      (node (ref "U11") (pin "4") (pinfunction "D2_4") (pintype "input"))
      (node (ref "U12") (pin "16") (pinfunction "Y2_16") (pintype "tri_state"))
      (node (ref "U13") (pin "5") (pinfunction "Y3_5") (pintype "tri_state"))
      (node (ref "U14") (pin "16") (pinfunction "Y2_16") (pintype "tri_state"))
      (node (ref "U15") (pin "5") (pinfunction "A4_5") (pintype "bidirectional"))
      (node (ref "U16") (pin "16") (pinfunction "4Q_16") (pintype "tri_state"))
      (node (ref "U21") (pin "12") (pinfunction "Y4_12") (pintype "tri_state"))
      (node (ref "U26") (pin "13") (pinfunction "D5_13") (pintype "input"))
    )
    (net (code "43") (name "BD4") (class "Default")
      (node (ref "PC0") (pin "47") (pinfunction "D4_47") (pintype "bidirectional"))
      (node (ref "U11") (pin "7") (pinfunction "D3_7") (pintype "input"))
      (node (ref "U12") (pin "7") (pinfunction "Y2_7") (pintype "tri_state"))
      (node (ref "U13") (pin "14") (pinfunction "Y3_14") (pintype "tri_state"))
      (node (ref "U14") (pin "7") (pinfunction "Y2_7") (pintype "tri_state"))
      (node (ref "U15") (pin "6") (pinfunction "A5_6") (pintype "bidirectional"))
      (node (ref "U16") (pin "15") (pinfunction "5Q_15") (pintype "tri_state"))
      (node (ref "U21") (pin "9") (pinfunction "Y1_9") (pintype "tri_state"))
      (node (ref "U26") (pin "8") (pinfunction "D4_8") (pintype "input"))
    )
    (net (code "44") (name "BD5") (class "Default")
      (node (ref "PC0") (pin "48") (pinfunction "D5_48") (pintype "bidirectional"))
      (node (ref "U11") (pin "14") (pinfunction "D6_14") (pintype "input"))
      (node (ref "U12") (pin "14") (pinfunction "Y3_14") (pintype "tri_state"))
      (node (ref "U13") (pin "7") (pinfunction "Y2_7") (pintype "tri_state"))
      (node (ref "U14") (pin "14") (pinfunction "Y3_14") (pintype "tri_state"))
      (node (ref "U15") (pin "7") (pinfunction "A6_7") (pintype "bidirectional"))
      (node (ref "U16") (pin "14") (pinfunction "6Q_14") (pintype "tri_state"))
      (node (ref "U21") (pin "7") (pinfunction "Y2_7") (pintype "tri_state"))
      (node (ref "U26") (pin "7") (pinfunction "D3_7") (pintype "input"))
    )
    (net (code "45") (name "BD6") (class "Default")
      (node (ref "PC0") (pin "49") (pinfunction "D6_49") (pintype "bidirectional"))
      (node (ref "U11") (pin "13") (pinfunction "D5_13") (pintype "input"))
      (node (ref "U12") (pin "9") (pinfunction "Y1_9") (pintype "tri_state"))
      (node (ref "U13") (pin "12") (pinfunction "Y4_12") (pintype "tri_state"))
      (node (ref "U14") (pin "9") (pinfunction "Y1_9") (pintype "tri_state"))
      (node (ref "U15") (pin "8") (pinfunction "A7_8") (pintype "bidirectional"))
      (node (ref "U16") (pin "13") (pinfunction "7Q_13") (pintype "tri_state"))
      (node (ref "U21") (pin "5") (pinfunction "Y3_5") (pintype "tri_state"))
      (node (ref "U26") (pin "4") (pinfunction "D2_4") (pintype "input"))
    )
    (net (code "46") (name "BD7") (class "Default")
      (node (ref "PC0") (pin "50") (pinfunction "D7_50") (pintype "bidirectional"))
      (node (ref "U11") (pin "8") (pinfunction "D4_8") (pintype "input"))
      (node (ref "U12") (pin "12") (pinfunction "Y4_12") (pintype "tri_state"))
      (node (ref "U13") (pin "9") (pinfunction "Y1_9") (pintype "tri_state"))
      (node (ref "U14") (pin "12") (pinfunction "Y4_12") (pintype "tri_state"))
      (node (ref "U15") (pin "9") (pinfunction "A8_9") (pintype "bidirectional"))
      (node (ref "U16") (pin "12") (pinfunction "8Q_12") (pintype "tri_state"))
      (node (ref "U21") (pin "3") (pinfunction "Y4_3") (pintype "tri_state"))
      (node (ref "U26") (pin "3") (pinfunction "D1_3") (pintype "input"))
    )
    (net (code "47") (name "CPUINH") (class "Default")
      (node (ref "U15") (pin "19") (pinfunction "G_19") (pintype "input"))
      (node (ref "U24") (pin "1") (pinfunction "G_1") (pintype "input"))
      (node (ref "U24") (pin "19") (pinfunction "G_19") (pintype "input"))
      (node (ref "U25") (pin "1") (pinfunction "G_1") (pintype "input"))
      (node (ref "U25") (pin "19") (pinfunction "G_19") (pintype "input"))
      (node (ref "U5") (pin "15") (pinfunction "G_15") (pintype "input"))
      (node (ref "U8") (pin "1") (pinfunction "G_1") (pintype "input"))
      (node (ref "U9") (pin "5") (pinfunction "Q_5") (pintype "output"))
    )
    (net (code "48") (name "GND") (class "Default")
      (node (ref "C1") (pin "2") (pinfunction "2_2") (pintype "passive"))
      (node (ref "C10") (pin "2") (pinfunction "2_2") (pintype "passive"))
      (node (ref "C11") (pin "2") (pinfunction "2_2") (pintype "passive"))
      (node (ref "C12") (pin "2") (pinfunction "2_2") (pintype "passive"))
      (node (ref "C13") (pin "2") (pinfunction "2_2") (pintype "passive"))
      (node (ref "C14") (pin "2") (pinfunction "2_2") (pintype "passive"))
      (node (ref "C15") (pin "2") (pinfunction "2_2") (pintype "passive"))
      (node (ref "C16") (pin "2") (pinfunction "2_2") (pintype "passive"))
      (node (ref "C17") (pin "2") (pinfunction "2_2") (pintype "passive"))
      (node (ref "C18") (pin "2") (pinfunction "2_2") (pintype "passive"))
      (node (ref "C19") (pin "2") (pinfunction "2_2") (pintype "passive"))
      (node (ref "C2") (pin "2") (pinfunction "2_2") (pintype "passive"))
      (node (ref "C20") (pin "2") (pinfunction "2_2") (pintype "passive"))
      (node (ref "C21") (pin "2") (pinfunction "2_2") (pintype "passive"))
      (node (ref "C22") (pin "2") (pinfunction "2_2") (pintype "passive"))
      (node (ref "C23") (pin "2") (pinfunction "2_2") (pintype "passive"))
      (node (ref "C24") (pin "2") (pinfunction "2_2") (pintype "passive"))
      (node (ref "C25") (pin "2") (pinfunction "2_2") (pintype "passive"))
      (node (ref "C26") (pin "2") (pinfunction "2_2") (pintype "passive"))
      (node (ref "C27") (pin "2") (pinfunction "2_2") (pintype "passive"))
      (node (ref "C28") (pin "2") (pinfunction "2_2") (pintype "passive"))
      (node (ref "C29") (pin "2") (pinfunction "2_2") (pintype "passive"))
      (node (ref "C3") (pin "2") (pinfunction "2_2") (pintype "passive"))
      (node (ref "C4") (pin "2") (pinfunction "2_2") (pintype "passive"))
      (node (ref "C5") (pin "2") (pinfunction "2_2") (pintype "passive"))
      (node (ref "C6") (pin "2") (pinfunction "2_2") (pintype "passive"))
      (node (ref "C7") (pin "2") (pinfunction "2_2") (pintype "passive"))
      (node (ref "C8") (pin "2") (pinfunction "2_2") (pintype "passive"))
      (node (ref "C9") (pin "2") (pinfunction "2_2") (pintype "passive"))
      (node (ref "D1") (pin "K") (pinfunction "C_K") (pintype "passive"))
      (node (ref "PC0") (pin "3") (pinfunction "GND_3") (pintype "bidirectional"))
      (node (ref "PC0") (pin "4") (pinfunction "GND_4") (pintype "bidirectional"))
      (node (ref "PC0") (pin "62") (pinfunction "GND_62") (pintype "bidirectional"))
      (node (ref "R4") (pin "1") (pinfunction "1_1") (pintype "passive"))
      (node (ref "U14") (pin "11") (pinfunction "A1_11") (pintype "input"))
      (node (ref "U14") (pin "13") (pinfunction "A2_13") (pintype "input"))
      (node (ref "U14") (pin "15") (pinfunction "A3_15") (pintype "input"))
      (node (ref "U14") (pin "17") (pinfunction "A4_17") (pintype "input"))
      (node (ref "U14") (pin "4") (pinfunction "A2_4") (pintype "input"))
      (node (ref "U14") (pin "6") (pinfunction "A3_6") (pintype "input"))
      (node (ref "U14") (pin "8") (pinfunction "A4_8") (pintype "input"))
      (node (ref "U16") (pin "2") (pinfunction "1D_2") (pintype "input"))
      (node (ref "U16") (pin "3") (pinfunction "2D_3") (pintype "input"))
      (node (ref "U16") (pin "8") (pinfunction "7D_8") (pintype "input"))
      (node (ref "U16") (pin "9") (pinfunction "8D_9") (pintype "input"))
      (node (ref "U23") (pin "5") (pinfunction "EI_5") (pintype "input"))
      (node (ref "U5") (pin "11") (pinfunction "3A_11") (pintype "input"))
      (node (ref "U5") (pin "14") (pinfunction "4A_14") (pintype "input"))
      (node (ref "U5") (pin "2") (pinfunction "1A_2") (pintype "input"))
      (node (ref "U5") (pin "5") (pinfunction "2A_5") (pintype "input"))
      (node (ref "U6") (pin "14") (pinfunction "Q5_14") (pintype "input"))
      (node (ref "U6") (pin "16") (pinfunction "Q6_16") (pintype "input"))
      (node (ref "U6") (pin "18") (pinfunction "Q7_18") (pintype "input"))
      (node (ref "U7") (pin "12") (pinfunction "Q4_12") (pintype "input"))
      (node (ref "U7") (pin "14") (pinfunction "Q5_14") (pintype "input"))
      (node (ref "U7") (pin "16") (pinfunction "Q6_16") (pintype "input"))
      (node (ref "U7") (pin "18") (pinfunction "Q7_18") (pintype "input"))
      (node (ref "U7") (pin "5") (pinfunction "Q1_5") (pintype "input"))
      (node (ref "U7") (pin "7") (pinfunction "Q2_7") (pintype "input"))
      (node (ref "U7") (pin "9") (pinfunction "Q3_9") (pintype "input"))
      (node (ref "U8") (pin "19") (pinfunction "G_19") (pintype "input"))
      (node (ref "U9") (pin "12") (pinfunction "D_12") (pintype "input"))
      (node (ref "Y1") (pin "4") (pinfunction "GND_4") (pintype "power_in"))
    )
    (net (code "49") (name "ID0") (class "Default")
      (node (ref "U13") (pin "2") (pinfunction "A1_2") (pintype "input"))
    )
    (net (code "50") (name "ID1") (class "Default")
      (node (ref "U13") (pin "17") (pinfunction "A4_17") (pintype "input"))
    )
    (net (code "51") (name "ID2") (class "Default")
      (node (ref "U13") (pin "4") (pinfunction "A2_4") (pintype "input"))
    )
    (net (code "52") (name "ID3") (class "Default")
      (node (ref "U13") (pin "15") (pinfunction "A3_15") (pintype "input"))
    )
    (net (code "53") (name "ID4") (class "Default")
      (node (ref "U13") (pin "6") (pinfunction "A3_6") (pintype "input"))
    )
    (net (code "54") (name "ID5") (class "Default")
      (node (ref "U13") (pin "13") (pinfunction "A2_13") (pintype "input"))
    )
    (net (code "55") (name "ID6") (class "Default")
      (node (ref "U13") (pin "8") (pinfunction "A4_8") (pintype "input"))
    )
    (net (code "56") (name "ID7") (class "Default")
      (node (ref "U13") (pin "11") (pinfunction "A1_11") (pintype "input"))
    )
    (net (code "57") (name "Net-(D1-PadA)") (class "Default")
      (node (ref "D1") (pin "A") (pinfunction "A_A") (pintype "passive"))
      (node (ref "R1") (pin "1") (pinfunction "1_1") (pintype "passive"))
    )
    (net (code "58") (name "Net-(Q1-B)") (class "Default")
      (node (ref "Q1") (pin "2") (pinfunction "B_2") (pintype "passive"))
      (node (ref "R2") (pin "2") (pinfunction "2_2") (pintype "passive"))
    )
    (net (code "59") (name "Net-(Q1-C)") (class "Default")
      (node (ref "Q1") (pin "3") (pinfunction "C_3") (pintype "passive"))
      (node (ref "R1") (pin "2") (pinfunction "2_2") (pintype "passive"))
    )
    (net (code "60") (name "Net-(U4A-O)") (class "Default")
      (node (ref "U4") (pin "2") (pinfunction "O_2") (pintype "output"))
      (node (ref "U7") (pin "1") (pinfunction "G_1") (pintype "input"))
    )
    (net (code "61") (name "Net-(U4B-I)") (class "Default")
      (node (ref "U4") (pin "12") (pinfunction "O_12") (pintype "output"))
      (node (ref "U4") (pin "3") (pinfunction "I_3") (pintype "input"))
    )
    (net (code "62") (name "Net-(U4B-O)") (class "Default")
      (node (ref "U4") (pin "4") (pinfunction "O_4") (pintype "output"))
      (node (ref "U9") (pin "3") (pinfunction "CLK_3") (pintype "input"))
    )
    (net (code "63") (name "Net-(U4D-I)") (class "Default")
      (node (ref "U4") (pin "9") (pinfunction "I_9") (pintype "input"))
      (node (ref "U7") (pin "19") (pinfunction "P=Q_19") (pintype "output"))
    )
    (net (code "64") (name "Net-(U4D-O)") (class "Default")
      (node (ref "U4") (pin "8") (pinfunction "O_8") (pintype "output"))
      (node (ref "U6") (pin "1") (pinfunction "G_1") (pintype "input"))
    )
    (net (code "65") (name "Net-(U5A-~{A}{slash}B)") (class "Default")
      (node (ref "JP1") (pin "2") (pinfunction "2_2") (pintype "passive"))
      (node (ref "R4") (pin "2") (pinfunction "2_2") (pintype "passive"))
      (node (ref "U5") (pin "1") (pinfunction "~{A}/B_1") (pintype "input"))
    )
    (net (code "66") (name "Net-(U6A-P=Q)") (class "Default")
      (node (ref "JP1") (pin "1") (pinfunction "1_1") (pintype "passive"))
      (node (ref "U6") (pin "19") (pinfunction "P=Q_19") (pintype "output"))
    )
    (net (code "67") (name "Net-(U8B-A4)") (class "Default")
      (node (ref "JP4") (pin "2") (pinfunction "2_2") (pintype "passive"))
      (node (ref "U8") (pin "17") (pinfunction "A4_17") (pintype "input"))
    )
    (net (code "68") (name "Net-(U8B-Y4)") (class "Default")
      (node (ref "JP3") (pin "2") (pinfunction "2_2") (pintype "passive"))
      (node (ref "U8") (pin "3") (pinfunction "Y4_3") (pintype "tri_state"))
    )
    (net (code "69") (name "Net-(U10A-CLK)") (class "Default")
      (node (ref "U10") (pin "3") (pinfunction "CLK_3") (pintype "input"))
      (node (ref "U4") (pin "6") (pinfunction "O_6") (pintype "output"))
    )
    (net (code "70") (name "Net-(U10A-~{Q})") (class "Default")
      (node (ref "JP2") (pin "1") (pinfunction "1_1") (pintype "passive"))
      (node (ref "U10") (pin "6") (pinfunction "~{Q}_6") (pintype "output"))
    )
    (net (code "71") (name "Net-(U10B-CLR)") (class "Default")
      (node (ref "U10") (pin "13") (pinfunction "CLR_13") (pintype "input"))
      (node (ref "U18") (pin "6") (pinfunction "O_6") (pintype "output"))
    )
    (net (code "72") (name "Net-(U11A-Q1)") (class "Default")
      (node (ref "U11") (pin "2") (pinfunction "Q1_2") (pintype "output"))
      (node (ref "U12") (pin "17") (pinfunction "A4_17") (pintype "input"))
      (node (ref "U5") (pin "3") (pinfunction "1B_3") (pintype "input"))
    )
    (net (code "73") (name "Net-(U11A-Q2)") (class "Default")
      (node (ref "U11") (pin "5") (pinfunction "Q2_5") (pintype "output"))
      (node (ref "U12") (pin "4") (pinfunction "A2_4") (pintype "input"))
      (node (ref "U5") (pin "13") (pinfunction "4B_13") (pintype "input"))
    )
    (net (code "74") (name "Net-(U11A-Q3)") (class "Default")
      (node (ref "U11") (pin "6") (pinfunction "Q3_6") (pintype "output"))
      (node (ref "U12") (pin "13") (pinfunction "A2_13") (pintype "input"))
      (node (ref "U4") (pin "1") (pinfunction "I_1") (pintype "input"))
    )
    (net (code "75") (name "Net-(U11A-Q4)") (class "Default")
      (node (ref "U11") (pin "9") (pinfunction "Q4_9") (pintype "output"))
      (node (ref "U12") (pin "8") (pinfunction "A4_8") (pintype "input"))
    )
    (net (code "76") (name "Net-(U11A-Q5)") (class "Default")
      (node (ref "U11") (pin "12") (pinfunction "Q5_12") (pintype "output"))
      (node (ref "U12") (pin "11") (pinfunction "A1_11") (pintype "input"))
    )
    (net (code "77") (name "Net-(U11A-Q6)") (class "Default")
      (node (ref "U11") (pin "15") (pinfunction "Q6_15") (pintype "output"))
      (node (ref "U12") (pin "6") (pinfunction "A3_6") (pintype "input"))
    )
    (net (code "78") (name "Net-(U11A-Q7)") (class "Default")
      (node (ref "U11") (pin "16") (pinfunction "Q7_16") (pintype "output"))
      (node (ref "U12") (pin "15") (pinfunction "A3_15") (pintype "input"))
      (node (ref "U5") (pin "10") (pinfunction "3B_10") (pintype "input"))
    )
    (net (code "79") (name "Net-(U11A-Q8)") (class "Default")
      (node (ref "U11") (pin "19") (pinfunction "Q8_19") (pintype "output"))
      (node (ref "U12") (pin "2") (pinfunction "A1_2") (pintype "input"))
      (node (ref "U5") (pin "6") (pinfunction "2B_6") (pintype "input"))
    )
    (net (code "80") (name "Net-(U13A-G)") (class "Default")
      (node (ref "U1") (pin "7") (pinfunction "Y7_7") (pintype "output"))
      (node (ref "U13") (pin "1") (pinfunction "G_1") (pintype "input"))
      (node (ref "U13") (pin "19") (pinfunction "G_19") (pintype "input"))
    )
    (net (code "81") (name "Net-(U14A-G)") (class "Default")
      (node (ref "U14") (pin "1") (pinfunction "G_1") (pintype "input"))
      (node (ref "U14") (pin "19") (pinfunction "G_19") (pintype "input"))
      (node (ref "U22") (pin "7") (pinfunction "Y7_7") (pintype "output"))
    )
    (net (code "82") (name "Net-(U15A-B1)") (class "Default")
      (node (ref "U15") (pin "18") (pinfunction "B1_18") (pintype "bidirectional"))
      (node (ref "U20") (pin "33") (pinfunction "D0_33") (pintype "bidirectional"))
    )
    (net (code "83") (name "Net-(U15A-B2)") (class "Default")
      (node (ref "U15") (pin "17") (pinfunction "B2_17") (pintype "bidirectional"))
      (node (ref "U20") (pin "32") (pinfunction "D1_32") (pintype "bidirectional"))
    )
    (net (code "84") (name "Net-(U15A-B3)") (class "Default")
      (node (ref "U15") (pin "16") (pinfunction "B3_16") (pintype "bidirectional"))
      (node (ref "U20") (pin "31") (pinfunction "D2_31") (pintype "bidirectional"))
    )
    (net (code "85") (name "Net-(U15A-B4)") (class "Default")
      (node (ref "U15") (pin "15") (pinfunction "B4_15") (pintype "bidirectional"))
      (node (ref "U20") (pin "30") (pinfunction "D3_30") (pintype "bidirectional"))
    )
    (net (code "86") (name "Net-(U15A-B5)") (class "Default")
      (node (ref "U15") (pin "14") (pinfunction "B5_14") (pintype "bidirectional"))
      (node (ref "U20") (pin "29") (pinfunction "D4_29") (pintype "bidirectional"))
    )
    (net (code "87") (name "Net-(U15A-B6)") (class "Default")
      (node (ref "U15") (pin "13") (pinfunction "B6_13") (pintype "bidirectional"))
      (node (ref "U20") (pin "28") (pinfunction "D5_28") (pintype "bidirectional"))
    )
    (net (code "88") (name "Net-(U15A-B7)") (class "Default")
      (node (ref "U15") (pin "12") (pinfunction "B7_12") (pintype "bidirectional"))
      (node (ref "U20") (pin "27") (pinfunction "D6_27") (pintype "bidirectional"))
    )
    (net (code "89") (name "Net-(U15A-B8)") (class "Default")
      (node (ref "U15") (pin "11") (pinfunction "B8_11") (pintype "bidirectional"))
      (node (ref "U20") (pin "26") (pinfunction "D7_26") (pintype "bidirectional"))
    )
    (net (code "90") (name "Net-(U15A-DIR)") (class "Default")
      (node (ref "U15") (pin "1") (pinfunction "DIR_1") (pintype "input"))
      (node (ref "U17") (pin "1") (pinfunction "I0_1") (pintype "input"))
      (node (ref "U19") (pin "3") (pinfunction "I_3") (pintype "input"))
      (node (ref "U20") (pin "34") (pinfunction "R~{WB}_34") (pintype "output"))
    )
    (net (code "91") (name "Net-(U16A-3D)") (class "Default")
      (node (ref "U16") (pin "4") (pinfunction "3D_4") (pintype "input"))
      (node (ref "U23") (pin "9") (pinfunction "A0_9") (pintype "output"))
    )
    (net (code "92") (name "Net-(U16A-4D)") (class "Default")
      (node (ref "U16") (pin "5") (pinfunction "4D_5") (pintype "input"))
      (node (ref "U23") (pin "7") (pinfunction "A1_7") (pintype "output"))
    )
    (net (code "93") (name "Net-(U16A-5D)") (class "Default")
      (node (ref "U16") (pin "6") (pinfunction "5D_6") (pintype "input"))
      (node (ref "U23") (pin "6") (pinfunction "A2_6") (pintype "output"))
    )
    (net (code "94") (name "Net-(U16A-6D)") (class "Default")
      (node (ref "U16") (pin "7") (pinfunction "6D_7") (pintype "input"))
      (node (ref "U19") (pin "10") (pinfunction "O_10") (pintype "output"))
    )
    (net (code "95") (name "Net-(U17A-I1)") (class "Default")
      (node (ref "JP3") (pin "3") (pinfunction "3_3") (pintype "passive"))
      (node (ref "JP4") (pin "1") (pinfunction "1_1") (pintype "passive"))
      (node (ref "U17") (pin "2") (pinfunction "I1_2") (pintype "input"))
      (node (ref "U17") (pin "4") (pinfunction "I0_4") (pintype "input"))
      (node (ref "U20") (pin "37") (pinfunction "PHI2_37") (pintype "input"))
      (node (ref "Y1") (pin "5") (pinfunction "OUT_5") (pintype "output"))
    )
    (net (code "96") (name "Net-(U17B-I1)") (class "Default")
      (node (ref "U17") (pin "5") (pinfunction "I1_5") (pintype "input"))
      (node (ref "U19") (pin "4") (pinfunction "O_4") (pintype "output"))
    )
    (net (code "97") (name "Net-(U17C-I0)") (class "Default")
      (node (ref "R6") (pin "2") (pinfunction "2_2") (pintype "passive"))
      (node (ref "U17") (pin "9") (pinfunction "I0_9") (pintype "input"))
      (node (ref "U19") (pin "2") (pinfunction "O_2") (pintype "output"))
    )
    (net (code "98") (name "Net-(U17C-I1)") (class "Default")
      (node (ref "U17") (pin "10") (pinfunction "I1_10") (pintype "input"))
      (node (ref "U19") (pin "12") (pinfunction "O_12") (pintype "output"))
    )
    (net (code "99") (name "Net-(U17D-I0)") (class "Default")
      (node (ref "U17") (pin "12") (pinfunction "I0_12") (pintype "input"))
      (node (ref "U18") (pin "11") (pinfunction "O_11") (pintype "output"))
    )
    (net (code "100") (name "Net-(U17D-I1)") (class "Default")
      (node (ref "U17") (pin "13") (pinfunction "I1_13") (pintype "input"))
      (node (ref "U19") (pin "6") (pinfunction "O_6") (pintype "output"))
    )
    (net (code "101") (name "Net-(U18A-I0)") (class "Default")
      (node (ref "U18") (pin "1") (pinfunction "I0_1") (pintype "input"))
      (node (ref "U4") (pin "10") (pinfunction "O_10") (pintype "output"))
    )
    (net (code "102") (name "Net-(U18A-O)") (class "Default")
      (node (ref "U18") (pin "3") (pinfunction "O_3") (pintype "output"))
      (node (ref "U9") (pin "2") (pinfunction "D_2") (pintype "input"))
    )
    (net (code "103") (name "Net-(U18C-O)") (class "Default")
      (node (ref "U18") (pin "8") (pinfunction "O_8") (pintype "output"))
      (node (ref "U20") (pin "4") (pinfunction "~{IRQB}_4") (pintype "input"))
    )
    (net (code "104") (name "Net-(U19A-I)") (class "Default")
      (node (ref "U19") (pin "1") (pinfunction "I_1") (pintype "input"))
      (node (ref "U3") (pin "12") (pinfunction "O_12") (pintype "output"))
    )
    (net (code "105") (name "Net-(U19D-I)") (class "Default")
      (node (ref "U19") (pin "9") (pinfunction "I_9") (pintype "input"))
      (node (ref "U20") (pin "7") (pinfunction "SYNC_7") (pintype "output"))
    )
    (net (code "106") (name "Net-(U19D-O)") (class "Default")
      (node (ref "U19") (pin "8") (pinfunction "O_8") (pintype "output"))
      (node (ref "U8") (pin "6") (pinfunction "A3_6") (pintype "input"))
    )
    (net (code "107") (name "Net-(U19E-I)") (class "Default")
      (node (ref "U19") (pin "11") (pinfunction "I_11") (pintype "input"))
      (node (ref "U23") (pin "15") (pinfunction "EO_15") (pintype "output"))
    )
    (net (code "108") (name "Net-(U20A-~{NMIB})") (class "Default")
      (node (ref "JP5") (pin "2") (pinfunction "2_2") (pintype "passive"))
      (node (ref "R5") (pin "1") (pinfunction "1_1") (pintype "passive"))
      (node (ref "U20") (pin "6") (pinfunction "~{NMIB}_6") (pintype "input"))
    )
    (net (code "109") (name "Net-(U21A-A1)") (class "Default")
      (node (ref "U21") (pin "2") (pinfunction "A1_2") (pintype "input"))
      (node (ref "U26") (pin "19") (pinfunction "Q8_19") (pintype "output"))
      (node (ref "U27") (pin "1") (pinfunction "I0_1") (pintype "input"))
    )
    (net (code "110") (name "Net-(U21A-A2)") (class "Default")
      (node (ref "U21") (pin "4") (pinfunction "A2_4") (pintype "input"))
      (node (ref "U26") (pin "16") (pinfunction "Q7_16") (pintype "output"))
      (node (ref "U27") (pin "4") (pinfunction "I0_4") (pintype "input"))
    )
    (net (code "111") (name "Net-(U21A-A3)") (class "Default")
      (node (ref "U21") (pin "6") (pinfunction "A3_6") (pintype "input"))
      (node (ref "U26") (pin "15") (pinfunction "Q6_15") (pintype "output"))
      (node (ref "U27") (pin "12") (pinfunction "I0_12") (pintype "input"))
    )
    (net (code "112") (name "Net-(U21A-A4)") (class "Default")
      (node (ref "U21") (pin "8") (pinfunction "A4_8") (pintype "input"))
      (node (ref "U26") (pin "12") (pinfunction "Q5_12") (pintype "output"))
      (node (ref "U27") (pin "9") (pinfunction "I0_9") (pintype "input"))
    )
    (net (code "113") (name "Net-(U21B-A1)") (class "Default")
      (node (ref "U21") (pin "11") (pinfunction "A1_11") (pintype "input"))
      (node (ref "U26") (pin "9") (pinfunction "Q4_9") (pintype "output"))
      (node (ref "U28") (pin "4") (pinfunction "I0_4") (pintype "input"))
    )
    (net (code "114") (name "Net-(U21B-A2)") (class "Default")
      (node (ref "U21") (pin "13") (pinfunction "A2_13") (pintype "input"))
      (node (ref "U26") (pin "6") (pinfunction "Q3_6") (pintype "output"))
      (node (ref "U28") (pin "1") (pinfunction "I0_1") (pintype "input"))
    )
    (net (code "115") (name "Net-(U21B-A3)") (class "Default")
      (node (ref "U21") (pin "15") (pinfunction "A3_15") (pintype "input"))
      (node (ref "U26") (pin "5") (pinfunction "Q2_5") (pintype "output"))
      (node (ref "U28") (pin "12") (pinfunction "I0_12") (pintype "input"))
    )
    (net (code "116") (name "Net-(U21B-A4)") (class "Default")
      (node (ref "U21") (pin "17") (pinfunction "A4_17") (pintype "input"))
      (node (ref "U26") (pin "2") (pinfunction "Q1_2") (pintype "output"))
      (node (ref "U28") (pin "9") (pinfunction "I0_9") (pintype "input"))
    )
    (net (code "117") (name "Net-(U23A-0)") (class "Default")
      (node (ref "U23") (pin "10") (pinfunction "0_10") (pintype "input"))
      (node (ref "U28") (pin "8") (pinfunction "O_8") (pintype "output"))
    )
    (net (code "118") (name "Net-(U23A-1)") (class "Default")
      (node (ref "U23") (pin "11") (pinfunction "1_11") (pintype "input"))
      (node (ref "U28") (pin "11") (pinfunction "O_11") (pintype "output"))
    )
    (net (code "119") (name "Net-(U23A-2)") (class "Default")
      (node (ref "U23") (pin "12") (pinfunction "2_12") (pintype "input"))
      (node (ref "U28") (pin "3") (pinfunction "O_3") (pintype "output"))
    )
    (net (code "120") (name "Net-(U23A-3)") (class "Default")
      (node (ref "U23") (pin "13") (pinfunction "3_13") (pintype "input"))
      (node (ref "U28") (pin "6") (pinfunction "O_6") (pintype "output"))
    )
    (net (code "121") (name "Net-(U23A-4)") (class "Default")
      (node (ref "U23") (pin "1") (pinfunction "4_1") (pintype "input"))
      (node (ref "U27") (pin "8") (pinfunction "O_8") (pintype "output"))
    )
    (net (code "122") (name "Net-(U23A-5)") (class "Default")
      (node (ref "U23") (pin "2") (pinfunction "5_2") (pintype "input"))
      (node (ref "U27") (pin "11") (pinfunction "O_11") (pintype "output"))
    )
    (net (code "123") (name "Net-(U23A-6)") (class "Default")
      (node (ref "U23") (pin "3") (pinfunction "6_3") (pintype "input"))
      (node (ref "U27") (pin "6") (pinfunction "O_6") (pintype "output"))
    )
    (net (code "124") (name "Net-(U23A-7)") (class "Default")
      (node (ref "U23") (pin "4") (pinfunction "7_4") (pintype "input"))
      (node (ref "U27") (pin "3") (pinfunction "O_3") (pintype "output"))
    )
    (net (code "125") (name "PH1") (class "Default")
      (node (ref "U16") (pin "11") (pinfunction "CLK_11") (pintype "input"))
      (node (ref "U20") (pin "3") (pinfunction "PHI1O_3") (pintype "output"))
      (node (ref "U9") (pin "11") (pinfunction "CLK_11") (pintype "input"))
    )
    (net (code "126") (name "PH2") (class "Default")
      (node (ref "U10") (pin "1") (pinfunction "CLR_1") (pintype "input"))
      (node (ref "U20") (pin "39") (pinfunction "PHI2O_39") (pintype "output"))
      (node (ref "U4") (pin "13") (pinfunction "I_13") (pintype "input"))
    )
    (net (code "127") (name "RDY") (class "Default")
      (node (ref "R6") (pin "1") (pinfunction "1_1") (pintype "passive"))
      (node (ref "U19") (pin "13") (pinfunction "I_13") (pintype "input"))
      (node (ref "U20") (pin "2") (pinfunction "RDY_2") (pintype "bidirectional"))
    )
    (net (code "128") (name "VCC") (class "Default")
      (node (ref "C1") (pin "1") (pinfunction "1_1") (pintype "passive"))
      (node (ref "C10") (pin "1") (pinfunction "1_1") (pintype "passive"))
      (node (ref "C11") (pin "1") (pinfunction "1_1") (pintype "passive"))
      (node (ref "C12") (pin "1") (pinfunction "1_1") (pintype "passive"))
      (node (ref "C13") (pin "1") (pinfunction "1_1") (pintype "passive"))
      (node (ref "C14") (pin "1") (pinfunction "1_1") (pintype "passive"))
      (node (ref "C15") (pin "1") (pinfunction "1_1") (pintype "passive"))
      (node (ref "C16") (pin "1") (pinfunction "1_1") (pintype "passive"))
      (node (ref "C17") (pin "1") (pinfunction "1_1") (pintype "passive"))
      (node (ref "C18") (pin "1") (pinfunction "1_1") (pintype "passive"))
      (node (ref "C19") (pin "1") (pinfunction "1_1") (pintype "passive"))
      (node (ref "C2") (pin "1") (pinfunction "1_1") (pintype "passive"))
      (node (ref "C20") (pin "1") (pinfunction "1_1") (pintype "passive"))
      (node (ref "C21") (pin "1") (pinfunction "1_1") (pintype "passive"))
      (node (ref "C22") (pin "1") (pinfunction "1_1") (pintype "passive"))
      (node (ref "C23") (pin "1") (pinfunction "1_1") (pintype "passive"))
      (node (ref "C24") (pin "1") (pinfunction "1_1") (pintype "passive"))
      (node (ref "C25") (pin "1") (pinfunction "1_1") (pintype "passive"))
      (node (ref "C26") (pin "1") (pinfunction "1_1") (pintype "passive"))
      (node (ref "C27") (pin "1") (pinfunction "1_1") (pintype "passive"))
      (node (ref "C28") (pin "1") (pinfunction "1_1") (pintype "passive"))
      (node (ref "C29") (pin "1") (pinfunction "1_1") (pintype "passive"))
      (node (ref "C3") (pin "1") (pinfunction "1_1") (pintype "passive"))
      (node (ref "C4") (pin "1") (pinfunction "1_1") (pintype "passive"))
      (node (ref "C5") (pin "1") (pinfunction "1_1") (pintype "passive"))
      (node (ref "C6") (pin "1") (pinfunction "1_1") (pintype "passive"))
      (node (ref "C7") (pin "1") (pinfunction "1_1") (pintype "passive"))
      (node (ref "C8") (pin "1") (pinfunction "1_1") (pintype "passive"))
      (node (ref "C9") (pin "1") (pinfunction "1_1") (pintype "passive"))
      (node (ref "PC0") (pin "5") (pinfunction "+5V_5") (pintype "bidirectional"))
      (node (ref "PC0") (pin "6") (pinfunction "+5V_6") (pintype "bidirectional"))
      (node (ref "Q1") (pin "1") (pinfunction "E_1") (pintype "passive"))
      (node (ref "R3") (pin "2") (pinfunction "2_2") (pintype "passive"))
      (node (ref "R5") (pin "2") (pinfunction "2_2") (pintype "passive"))
      (node (ref "U10") (pin "11") (pinfunction "CLK_11") (pintype "input"))
      (node (ref "U10") (pin "12") (pinfunction "D_12") (pintype "input"))
      (node (ref "U10") (pin "2") (pinfunction "D_2") (pintype "input"))
      (node (ref "U10") (pin "4") (pinfunction "PRE_4") (pintype "input"))
      (node (ref "U14") (pin "2") (pinfunction "A1_2") (pintype "input"))
      (node (ref "U2") (pin "6") (pinfunction "G1_6") (pintype "input"))
      (node (ref "U20") (pin "36") (pinfunction "BE_36") (pintype "input"))
      (node (ref "U20") (pin "38") (pinfunction "~{SOB}_38") (pintype "input"))
      (node (ref "U22") (pin "6") (pinfunction "G1_6") (pintype "input"))
      (node (ref "U3") (pin "10") (pinfunction "I1_10") (pintype "input"))
      (node (ref "U3") (pin "11") (pinfunction "I2_11") (pintype "input"))
      (node (ref "U3") (pin "3") (pinfunction "I0_3") (pintype "input"))
      (node (ref "U3") (pin "4") (pinfunction "I1_4") (pintype "input"))
      (node (ref "U3") (pin "5") (pinfunction "I2_5") (pintype "input"))
      (node (ref "U3") (pin "9") (pinfunction "I0_9") (pintype "input"))
      (node (ref "U6") (pin "11") (pinfunction "P4_11") (pintype "input"))
      (node (ref "U6") (pin "12") (pinfunction "Q4_12") (pintype "input"))
      (node (ref "U6") (pin "2") (pinfunction "P0_2") (pintype "input"))
      (node (ref "U6") (pin "3") (pinfunction "Q0_3") (pintype "input"))
      (node (ref "U6") (pin "4") (pinfunction "P1_4") (pintype "input"))
      (node (ref "U6") (pin "5") (pinfunction "Q1_5") (pintype "input"))
      (node (ref "U6") (pin "6") (pinfunction "P2_6") (pintype "input"))
      (node (ref "U6") (pin "7") (pinfunction "Q2_7") (pintype "input"))
      (node (ref "U6") (pin "8") (pinfunction "P3_8") (pintype "input"))
      (node (ref "U6") (pin "9") (pinfunction "Q3_9") (pintype "input"))
      (node (ref "U7") (pin "2") (pinfunction "P0_2") (pintype "input"))
      (node (ref "U7") (pin "3") (pinfunction "Q0_3") (pintype "input"))
      (node (ref "U8") (pin "8") (pinfunction "A4_8") (pintype "input"))
      (node (ref "U9") (pin "4") (pinfunction "PRE_4") (pintype "input"))
      (node (ref "Y1") (pin "8") (pinfunction "VCC_8") (pintype "power_in"))
    )
    (net (code "129") (name "unconnected-(PC0-+3.3V-Pad2)") (class "Default")
      (node (ref "PC0") (pin "2") (pinfunction "+3.3V_2") (pintype "bidirectional"))
    )
    (net (code "130") (name "unconnected-(PC0-+5VSB-Pad8)") (class "Default")
      (node (ref "PC0") (pin "8") (pinfunction "+5VSB_8") (pintype "bidirectional"))
    )
    (net (code "131") (name "unconnected-(PC0-+12V-Pad1)") (class "Default")
      (node (ref "PC0") (pin "1") (pinfunction "+12V_1") (pintype "bidirectional"))
    )
    (net (code "132") (name "unconnected-(PC0--12V-Pad7)") (class "Default")
      (node (ref "PC0") (pin "7") (pinfunction "-12V_7") (pintype "bidirectional"))
    )
    (net (code "133") (name "unconnected-(PC0-CLKAUX-Pad16)") (class "Default")
      (node (ref "PC0") (pin "16") (pinfunction "CLKAUX_16") (pintype "bidirectional"))
    )
    (net (code "134") (name "unconnected-(PC0-~{BUSRQ}-Pad10)") (class "Default")
      (node (ref "PC0") (pin "10") (pinfunction "~{BUSRQ}_10") (pintype "bidirectional"))
    )
    (net (code "135") (name "unconnected-(PC0-~{CINH}-Pad13)") (class "Default")
      (node (ref "PC0") (pin "13") (pinfunction "~{CINH}_13") (pintype "bidirectional"))
    )
    (net (code "136") (name "unconnected-(U1A-Y0-Pad15)") (class "Default")
      (node (ref "U1") (pin "15") (pinfunction "Y0_15") (pintype "output"))
    )
    (net (code "137") (name "unconnected-(U1A-Y1-Pad14)") (class "Default")
      (node (ref "U1") (pin "14") (pinfunction "Y1_14") (pintype "output"))
    )
    (net (code "138") (name "unconnected-(U1A-Y2-Pad13)") (class "Default")
      (node (ref "U1") (pin "13") (pinfunction "Y2_13") (pintype "output"))
    )
    (net (code "139") (name "unconnected-(U1A-Y3-Pad12)") (class "Default")
      (node (ref "U1") (pin "12") (pinfunction "Y3_12") (pintype "output"))
    )
    (net (code "140") (name "unconnected-(U1A-Y4-Pad11)") (class "Default")
      (node (ref "U1") (pin "11") (pinfunction "Y4_11") (pintype "output"))
    )
    (net (code "141") (name "unconnected-(U1A-Y5-Pad10)") (class "Default")
      (node (ref "U1") (pin "10") (pinfunction "Y5_10") (pintype "output"))
    )
    (net (code "142") (name "unconnected-(U1A-Y6-Pad9)") (class "Default")
      (node (ref "U1") (pin "9") (pinfunction "Y6_9") (pintype "output"))
    )
    (net (code "143") (name "unconnected-(U2A-Y0-Pad15)") (class "Default")
      (node (ref "U2") (pin "15") (pinfunction "Y0_15") (pintype "output"))
    )
    (net (code "144") (name "unconnected-(U2A-Y1-Pad14)") (class "Default")
      (node (ref "U2") (pin "14") (pinfunction "Y1_14") (pintype "output"))
    )
    (net (code "145") (name "unconnected-(U2A-Y6-Pad9)") (class "Default")
      (node (ref "U2") (pin "9") (pinfunction "Y6_9") (pintype "output"))
    )
    (net (code "146") (name "unconnected-(U2A-Y7-Pad7)") (class "Default")
      (node (ref "U2") (pin "7") (pinfunction "Y7_7") (pintype "output"))
    )
    (net (code "147") (name "unconnected-(U3B-O-Pad6)") (class "Default")
      (node (ref "U3") (pin "6") (pinfunction "O_6") (pintype "output"))
    )
    (net (code "148") (name "unconnected-(U3C-O-Pad8)") (class "Default")
      (node (ref "U3") (pin "8") (pinfunction "O_8") (pintype "output"))
    )
    (net (code "149") (name "unconnected-(U8A-Y4-Pad12)") (class "Default")
      (node (ref "U8") (pin "12") (pinfunction "Y4_12") (pintype "tri_state"))
    )
    (net (code "150") (name "unconnected-(U9B-Q-Pad9)") (class "Default")
      (node (ref "U9") (pin "9") (pinfunction "Q_9") (pintype "output"))
    )
    (net (code "151") (name "unconnected-(U10A-Q-Pad5)") (class "Default")
      (node (ref "U10") (pin "5") (pinfunction "Q_5") (pintype "output"))
    )
    (net (code "152") (name "unconnected-(U10B-Q-Pad9)") (class "Default")
      (node (ref "U10") (pin "9") (pinfunction "Q_9") (pintype "output"))
    )
    (net (code "153") (name "unconnected-(U22A-Y0-Pad15)") (class "Default")
      (node (ref "U22") (pin "15") (pinfunction "Y0_15") (pintype "output"))
    )
    (net (code "154") (name "unconnected-(U22A-Y1-Pad14)") (class "Default")
      (node (ref "U22") (pin "14") (pinfunction "Y1_14") (pintype "output"))
    )
    (net (code "155") (name "unconnected-(U22A-Y2-Pad13)") (class "Default")
      (node (ref "U22") (pin "13") (pinfunction "Y2_13") (pintype "output"))
    )
    (net (code "156") (name "unconnected-(U22A-Y3-Pad12)") (class "Default")
      (node (ref "U22") (pin "12") (pinfunction "Y3_12") (pintype "output"))
    )
    (net (code "157") (name "unconnected-(U22A-Y4-Pad11)") (class "Default")
      (node (ref "U22") (pin "11") (pinfunction "Y4_11") (pintype "output"))
    )
    (net (code "158") (name "unconnected-(U22A-Y5-Pad10)") (class "Default")
      (node (ref "U22") (pin "10") (pinfunction "Y5_10") (pintype "output"))
    )
    (net (code "159") (name "~{BBUSACK}") (class "Default")
      (node (ref "PC0") (pin "20") (pinfunction "~{BUSACK}_20") (pintype "bidirectional"))
      (node (ref "U8") (pin "7") (pinfunction "Y2_7") (pintype "tri_state"))
    )
    (net (code "160") (name "~{BCBR}") (class "Default")
      (node (ref "PC0") (pin "12") (pinfunction "~{CBR}_12") (pintype "bidirectional"))
      (node (ref "U4") (pin "11") (pinfunction "I_11") (pintype "input"))
    )
    (net (code "161") (name "~{BCSX}") (class "Default")
      (node (ref "PC0") (pin "9") (pinfunction "~{CSX}_9") (pintype "bidirectional"))
      (node (ref "U1") (pin "4") (pinfunction "G2A_4") (pintype "input"))
      (node (ref "U2") (pin "5") (pinfunction "G2B_5") (pintype "input"))
    )
    (net (code "162") (name "~{BFETCH}") (class "Default")
      (node (ref "PC0") (pin "19") (pinfunction "~{FETCH}_19") (pintype "bidirectional"))
      (node (ref "U8") (pin "14") (pinfunction "Y3_14") (pintype "tri_state"))
    )
    (net (code "163") (name "~{BHALT}") (class "Default")
      (node (ref "PC0") (pin "17") (pinfunction "~{HALT}_17") (pintype "bidirectional"))
      (node (ref "U8") (pin "5") (pinfunction "Y3_5") (pintype "tri_state"))
    )
    (net (code "164") (name "~{BINH}") (class "Default")
      (node (ref "PC0") (pin "11") (pinfunction "~{INH}_11") (pintype "bidirectional"))
      (node (ref "U17") (pin "11") (pinfunction "O_11") (pintype "output"))
    )
    (net (code "165") (name "~{BINT}") (class "Default")
      (node (ref "PC0") (pin "51") (pinfunction "~{INT}_51") (pintype "bidirectional"))
      (node (ref "U18") (pin "10") (pinfunction "I1_10") (pintype "input"))
    )
    (net (code "166") (name "~{BIRQ0}") (class "Default")
      (node (ref "PC0") (pin "53") (pinfunction "~{IRQ0}_53") (pintype "bidirectional"))
      (node (ref "U27") (pin "2") (pinfunction "I1_2") (pintype "input"))
    )
    (net (code "167") (name "~{BIRQ1}") (class "Default")
      (node (ref "PC0") (pin "54") (pinfunction "~{IRQ1}_54") (pintype "bidirectional"))
      (node (ref "U27") (pin "5") (pinfunction "I1_5") (pintype "input"))
    )
    (net (code "168") (name "~{BIRQ2}") (class "Default")
      (node (ref "PC0") (pin "55") (pinfunction "~{IRQ2}_55") (pintype "bidirectional"))
      (node (ref "U27") (pin "13") (pinfunction "I1_13") (pintype "input"))
    )
    (net (code "169") (name "~{BIRQ3}") (class "Default")
      (node (ref "PC0") (pin "56") (pinfunction "~{IRQ3}_56") (pintype "bidirectional"))
      (node (ref "U27") (pin "10") (pinfunction "I1_10") (pintype "input"))
    )
    (net (code "170") (name "~{BIRQ4}") (class "Default")
      (node (ref "PC0") (pin "57") (pinfunction "~{IRQ4}_57") (pintype "bidirectional"))
      (node (ref "U28") (pin "5") (pinfunction "I1_5") (pintype "input"))
    )
    (net (code "171") (name "~{BIRQ5}") (class "Default")
      (node (ref "PC0") (pin "58") (pinfunction "~{IRQ5}_58") (pintype "bidirectional"))
      (node (ref "U28") (pin "2") (pinfunction "I1_2") (pintype "input"))
    )
    (net (code "172") (name "~{BIRQ6}") (class "Default")
      (node (ref "PC0") (pin "59") (pinfunction "~{IRQ6}_59") (pintype "bidirectional"))
      (node (ref "U28") (pin "13") (pinfunction "I1_13") (pintype "input"))
    )
    (net (code "173") (name "~{BIRQ7}") (class "Default")
      (node (ref "PC0") (pin "60") (pinfunction "~{IRQ7}_60") (pintype "bidirectional"))
      (node (ref "U28") (pin "10") (pinfunction "I1_10") (pintype "input"))
    )
    (net (code "174") (name "~{BIRQX}") (class "Default")
      (node (ref "PC0") (pin "52") (pinfunction "~{IRQX}_52") (pintype "bidirectional"))
      (node (ref "U10") (pin "8") (pinfunction "~{Q}_8") (pintype "output"))
    )
    (net (code "175") (name "~{BNMI}") (class "Default")
      (node (ref "JP5") (pin "1") (pinfunction "1_1") (pintype "passive"))
      (node (ref "PC0") (pin "61") (pinfunction "~{NMI}_61") (pintype "bidirectional"))
    )
    (net (code "176") (name "~{BRD}") (class "Default")
      (node (ref "PC0") (pin "21") (pinfunction "~{RD}_21") (pintype "bidirectional"))
      (node (ref "U1") (pin "5") (pinfunction "G2B_5") (pintype "input"))
      (node (ref "U2") (pin "2") (pinfunction "B_2") (pintype "input"))
      (node (ref "U8") (pin "18") (pinfunction "Y1_18") (pintype "tri_state"))
    )
    (net (code "177") (name "~{BRST}") (class "Default")
      (node (ref "PC0") (pin "14") (pinfunction "~{RST}_14") (pintype "bidirectional"))
      (node (ref "U8") (pin "11") (pinfunction "A1_11") (pintype "input"))
    )
    (net (code "178") (name "~{BUSACK}") (class "Default")
      (node (ref "U10") (pin "10") (pinfunction "PRE_10") (pintype "input"))
      (node (ref "U8") (pin "13") (pinfunction "A2_13") (pintype "input"))
      (node (ref "U9") (pin "10") (pinfunction "PRE_10") (pintype "input"))
      (node (ref "U9") (pin "6") (pinfunction "~{Q}_6") (pintype "output"))
    )
    (net (code "179") (name "~{BWAIT}") (class "Default")
      (node (ref "PC0") (pin "18") (pinfunction "~{WAIT}_18") (pintype "bidirectional"))
      (node (ref "U3") (pin "1") (pinfunction "I0_1") (pintype "input"))
    )
    (net (code "180") (name "~{BWR}") (class "Default")
      (node (ref "PC0") (pin "22") (pinfunction "~{WR}_22") (pintype "bidirectional"))
      (node (ref "U2") (pin "3") (pinfunction "C_3") (pintype "input"))
      (node (ref "U8") (pin "16") (pinfunction "Y2_16") (pintype "tri_state"))
    )
    (net (code "181") (name "~{CS0_READ}") (class "Default")
      (node (ref "U12") (pin "1") (pinfunction "G_1") (pintype "input"))
      (node (ref "U12") (pin "19") (pinfunction "G_19") (pintype "input"))
      (node (ref "U2") (pin "11") (pinfunction "Y4_11") (pintype "output"))
    )
    (net (code "182") (name "~{CS0_WRITE}") (class "Default")
      (node (ref "U11") (pin "11") (pinfunction "CLK_11") (pintype "input"))
      (node (ref "U2") (pin "13") (pinfunction "Y2_13") (pintype "output"))
      (node (ref "U4") (pin "5") (pinfunction "I_5") (pintype "input"))
    )
    (net (code "183") (name "~{CS1_READ}") (class "Default")
      (node (ref "U2") (pin "10") (pinfunction "Y5_10") (pintype "output"))
      (node (ref "U21") (pin "1") (pinfunction "G_1") (pintype "input"))
      (node (ref "U21") (pin "19") (pinfunction "G_19") (pintype "input"))
    )
    (net (code "184") (name "~{CS1_WRITE}") (class "Default")
      (node (ref "U2") (pin "12") (pinfunction "Y3_12") (pintype "output"))
      (node (ref "U26") (pin "11") (pinfunction "CLK_11") (pintype "input"))
    )
    (net (code "185") (name "~{HALT}") (class "Default")
      (node (ref "R2") (pin "1") (pinfunction "1_1") (pintype "passive"))
      (node (ref "U17") (pin "8") (pinfunction "O_8") (pintype "output"))
      (node (ref "U8") (pin "15") (pinfunction "A3_15") (pintype "input"))
    )
    (net (code "186") (name "~{IVG}") (class "Default")
      (node (ref "U18") (pin "9") (pinfunction "I0_9") (pintype "input"))
      (node (ref "U23") (pin "14") (pinfunction "GS_14") (pintype "output"))
    )
    (net (code "187") (name "~{IVP}") (class "Default")
      (node (ref "U16") (pin "1") (pinfunction "OC_1") (pintype "input"))
      (node (ref "U18") (pin "4") (pinfunction "I0_4") (pintype "input"))
      (node (ref "U22") (pin "9") (pinfunction "Y6_9") (pintype "output"))
    )
    (net (code "188") (name "~{MLB}") (class "Default")
      (node (ref "U18") (pin "2") (pinfunction "I1_2") (pintype "input"))
      (node (ref "U20") (pin "5") (pinfunction "~{MLB}_5") (pintype "output"))
    )
    (net (code "189") (name "~{RD}") (class "Default")
      (node (ref "U17") (pin "3") (pinfunction "O_3") (pintype "output"))
      (node (ref "U22") (pin "5") (pinfunction "G2B_5") (pintype "input"))
      (node (ref "U8") (pin "2") (pinfunction "A1_2") (pintype "input"))
    )
    (net (code "190") (name "~{RST}") (class "Default")
      (node (ref "U11") (pin "1") (pinfunction "CLR_1") (pintype "input"))
      (node (ref "U18") (pin "5") (pinfunction "I1_5") (pintype "input"))
      (node (ref "U20") (pin "40") (pinfunction "~{RESB}_40") (pintype "input"))
      (node (ref "U26") (pin "1") (pinfunction "CLR_1") (pintype "input"))
      (node (ref "U8") (pin "9") (pinfunction "Y1_9") (pintype "tri_state"))
      (node (ref "U9") (pin "1") (pinfunction "CLR_1") (pintype "input"))
      (node (ref "U9") (pin "13") (pinfunction "CLR_13") (pintype "input"))
    )
    (net (code "191") (name "~{VPB}") (class "Default")
      (node (ref "U19") (pin "5") (pinfunction "I_5") (pintype "input"))
      (node (ref "U20") (pin "1") (pinfunction "~{VPB}_1") (pintype "output"))
      (node (ref "U22") (pin "4") (pinfunction "G2A_4") (pintype "input"))
    )
    (net (code "192") (name "~{WAIT_BANKSW}") (class "Default")
      (node (ref "JP2") (pin "2") (pinfunction "2_2") (pintype "passive"))
      (node (ref "R3") (pin "1") (pinfunction "1_1") (pintype "passive"))
      (node (ref "U3") (pin "2") (pinfunction "I1_2") (pintype "input"))
    )
    (net (code "193") (name "~{WAIT_DMA}") (class "Default")
      (node (ref "U3") (pin "13") (pinfunction "I2_13") (pintype "input"))
      (node (ref "U9") (pin "8") (pinfunction "~{Q}_8") (pintype "output"))
    )
    (net (code "194") (name "~{WR}") (class "Default")
      (node (ref "U17") (pin "6") (pinfunction "O_6") (pintype "output"))
      (node (ref "U8") (pin "4") (pinfunction "A2_4") (pintype "input"))
    )
  )
)
